# 4040M_V1_0_-_ESP32.net
KiCad netlist of a schematic drawn in EasyEDA Pro
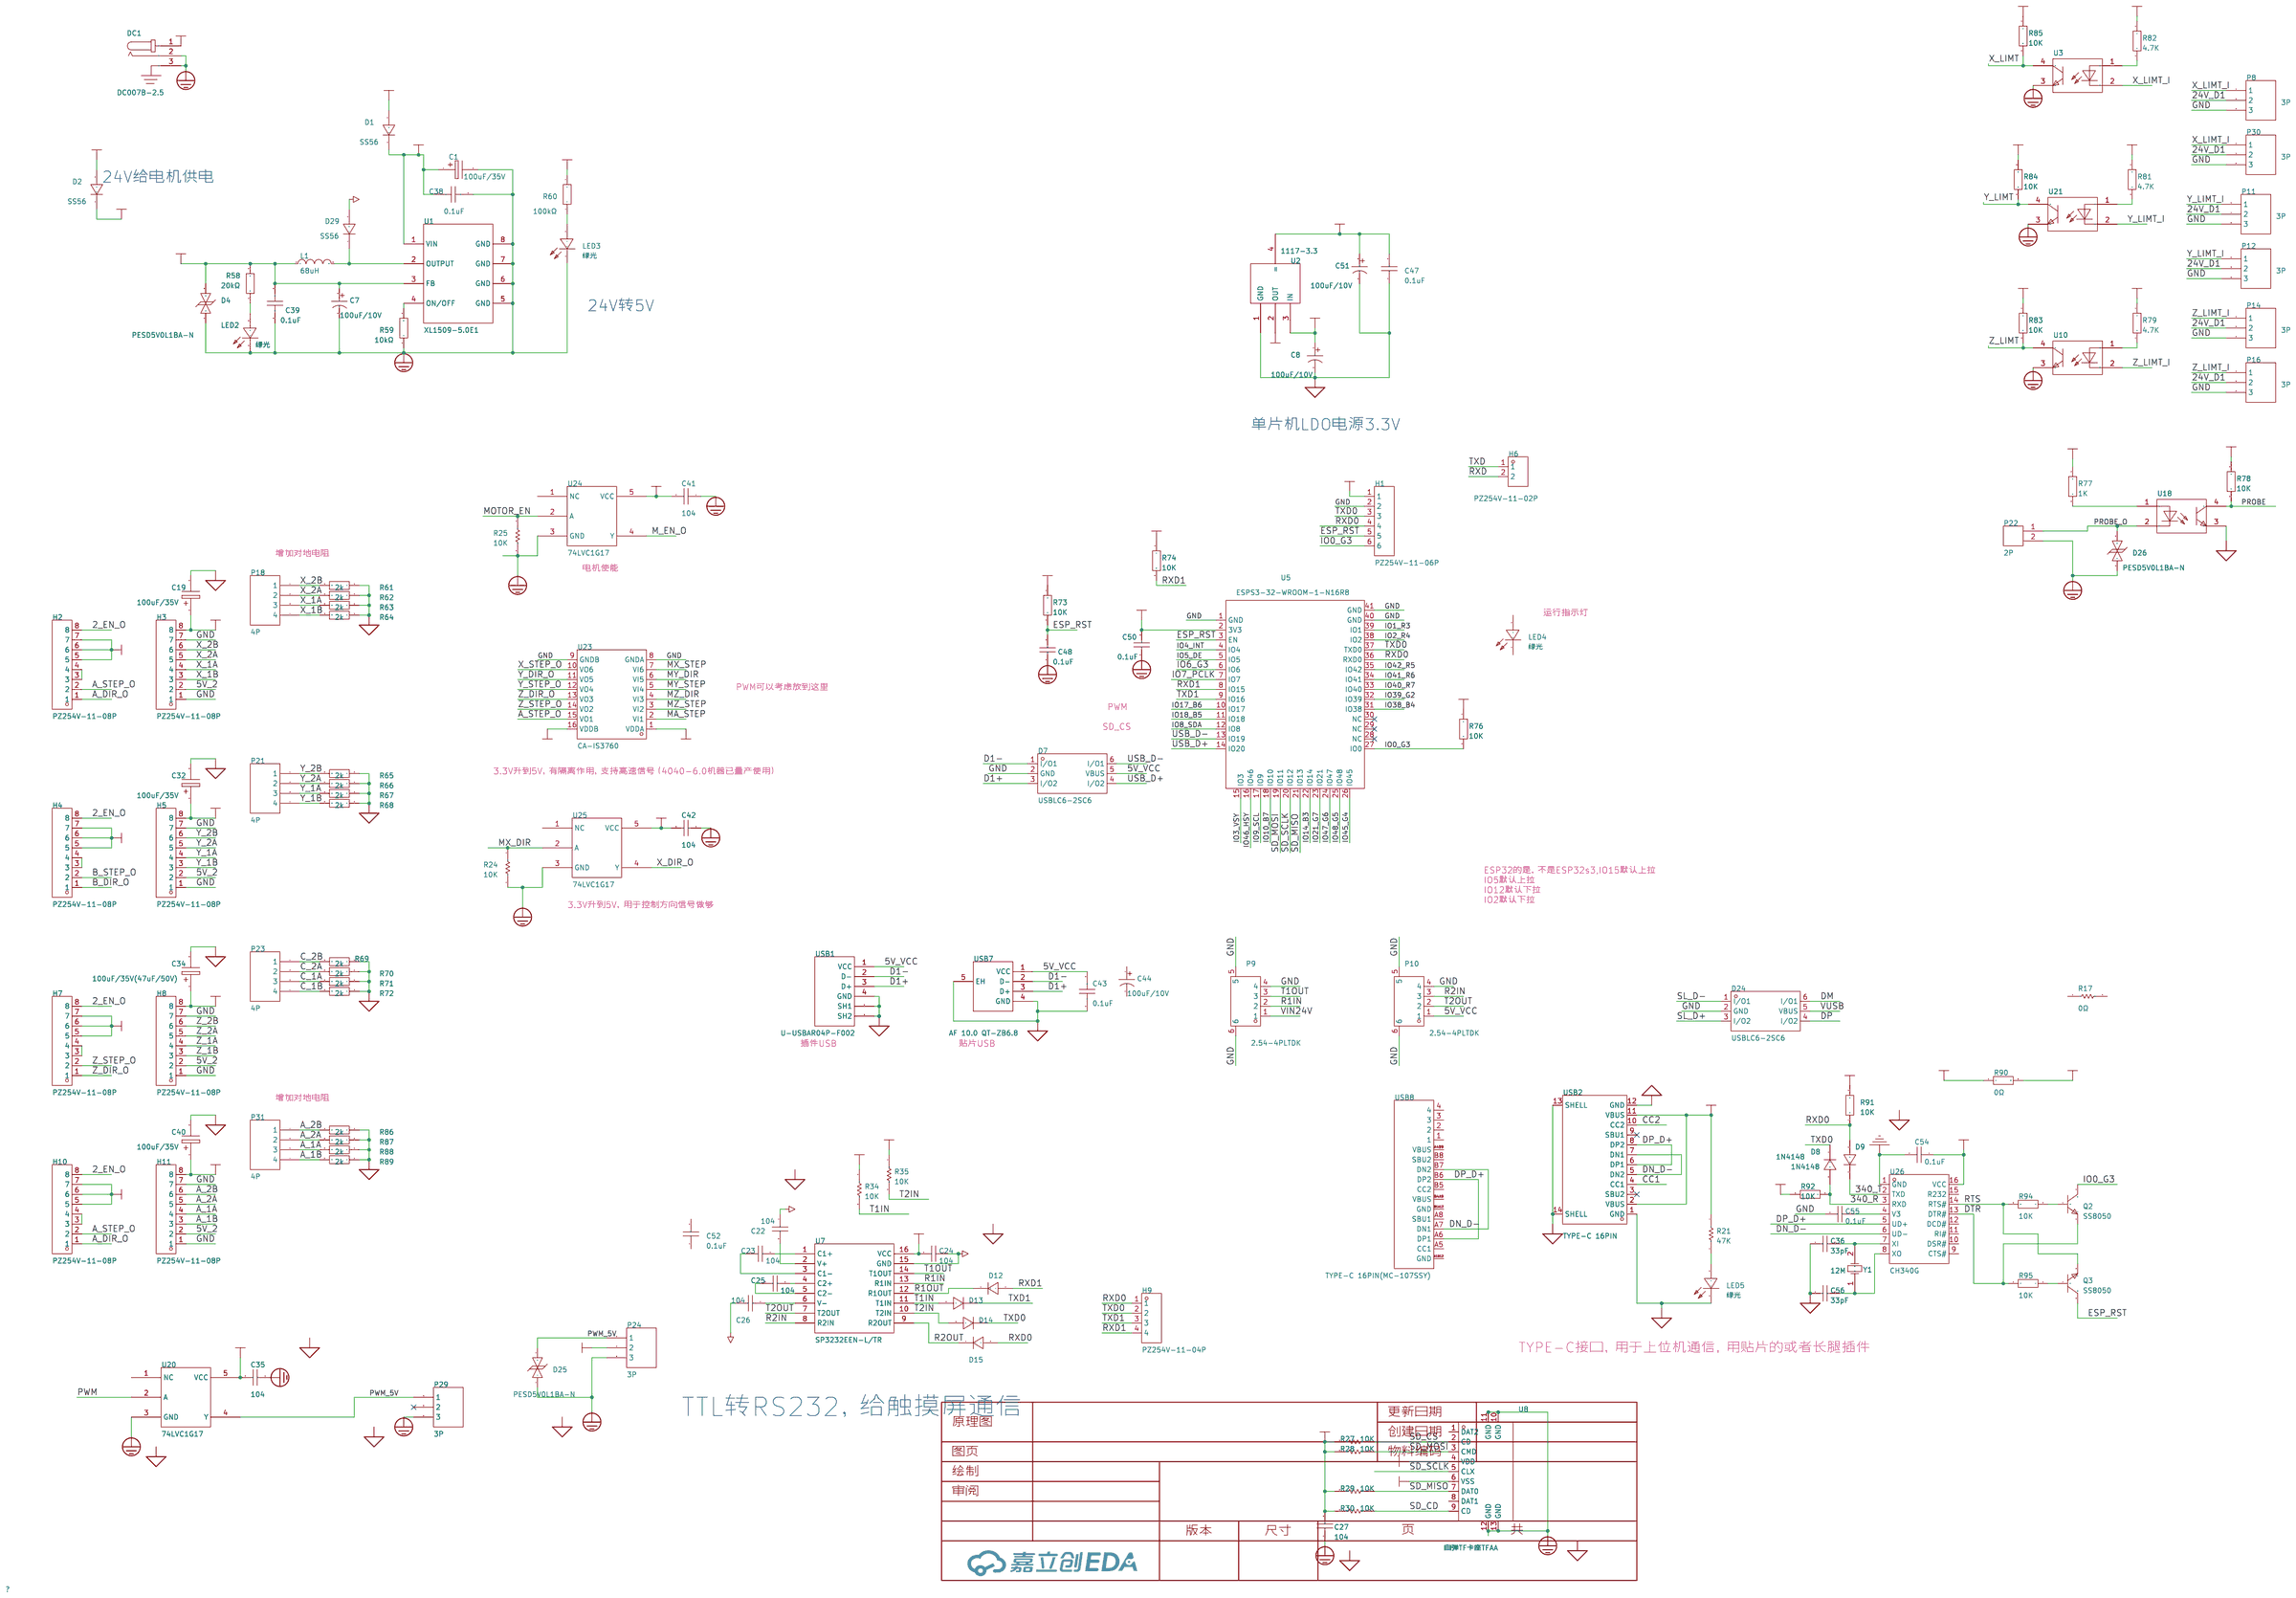
[diagram p0: schematic sheet]

(export (version "E")
  (design (tool "Eeschema 10.0.6"))
  (components
    (comp (ref "C1")
      (value "100uF/35V")
      (footprint "easyedapro:电解电容贴片10x10")
      (libsource (lib "easyedapro") (part "ELECTRO1"))
    )
    (comp (ref "C7")
      (value "100uF/10V")
      (footprint "easyedapro:CAP-SMD_BD5.0-L5.3-W5.3-RD")
      (fields (field (name "Manufacturer Part") "CS1A101M-CRD54") (field (name "Manufacturer") "ST(先科)"))
      (libsource (lib "easyedapro") (part "CS1A101M-CRD54"))
    )
    (comp (ref "C8")
      (value "100uF/10V")
      (footprint "easyedapro:CAP-SMD_BD5.0-L5.3-W5.3-RD")
      (fields (field (name "Manufacturer Part") "CS1A101M-CRD54") (field (name "Manufacturer") "ST(先科)"))
      (libsource (lib "easyedapro") (part "CS1A101M-CRD54"))
    )
    (comp (ref "C19")
      (value "100uF/35V")
      (footprint "easyedapro:电解电容贴片10x10")
      (libsource (lib "easyedapro") (part "ELECTRO1"))
    )
    (comp (ref "C22")
      (value "104")
      (footprint "easyedapro:0603C")
      (description "Capacitor (Semiconductor SIM Model)")
      (libsource (lib "easyedapro") (part "Cap Semi"))
    )
    (comp (ref "C23")
      (value "104")
      (footprint "easyedapro:0603C")
      (description "Capacitor (Semiconductor SIM Model)")
      (libsource (lib "easyedapro") (part "Cap Semi"))
    )
    (comp (ref "C24")
      (value "104")
      (footprint "easyedapro:0603C")
      (description "Capacitor (Semiconductor SIM Model)")
      (libsource (lib "easyedapro") (part "Cap Semi"))
    )
    (comp (ref "C25")
      (value "104")
      (footprint "easyedapro:0603C")
      (description "Capacitor (Semiconductor SIM Model)")
      (libsource (lib "easyedapro") (part "Cap Semi"))
    )
    (comp (ref "C26")
      (value "104")
      (footprint "easyedapro:0603C")
      (description "Capacitor (Semiconductor SIM Model)")
      (libsource (lib "easyedapro") (part "Cap Semi"))
    )
    (comp (ref "C27")
      (value "104")
      (footprint "easyedapro:11")
      (description "Capacitor (Semiconductor SIM Model)")
      (libsource (lib "easyedapro") (part "Cap Semi"))
    )
    (comp (ref "C32")
      (value "100uF/35V")
      (footprint "easyedapro:电解电容贴片10x10")
      (libsource (lib "easyedapro") (part "ELECTRO1"))
    )
    (comp (ref "C34")
      (value "100uF/35V(47uF/50V)")
      (footprint "easyedapro:电解电容贴片10x10")
      (libsource (lib "easyedapro") (part "ELECTRO1"))
    )
    (comp (ref "C35")
      (value "104")
      (footprint "easyedapro:0603C")
      (description "Capacitor (Semiconductor SIM Model)")
      (libsource (lib "easyedapro") (part "Cap Semi"))
    )
    (comp (ref "C36")
      (value "33pF")
      (footprint "easyedapro:C0603")
      (description "容值:12pF;精度:±5%;额定电压:50V;温度系数:C0G;")
      (fields
        (field (name "Manufacturer Part") "CL10C120JB8NNNC")
        (field (name "Manufacturer") "SAMSUNG(三星)")
      )
      (libsource (lib "easyedapro") (part "CL10C120JB8NNNC"))
    )
    (comp (ref "C38")
      (value "0.1uF")
      (footprint "easyedapro:C0603")
      (description "容值:8.2nF;精度:±10%;额定电压:50V;温度系数:X7R;")
      (fields (field (name "Manufacturer Part") "0603B822K500NT") (field (name "Manufacturer") "FH(风华)"))
      (libsource (lib "easyedapro") (part "0603B822K500NT"))
    )
    (comp (ref "C39")
      (value "0.1uF")
      (footprint "easyedapro:C0603")
      (description "容值:8.2nF;精度:±10%;额定电压:50V;温度系数:X7R;")
      (fields (field (name "Manufacturer Part") "0603B822K500NT") (field (name "Manufacturer") "FH(风华)"))
      (libsource (lib "easyedapro") (part "0603B822K500NT"))
    )
    (comp (ref "C40")
      (value "100uF/35V")
      (footprint "easyedapro:电解电容贴片10x10")
      (libsource (lib "easyedapro") (part "ELECTRO1"))
    )
    (comp (ref "C41")
      (value "104")
      (footprint "easyedapro:0603C")
      (description "Capacitor (Semiconductor SIM Model)")
      (libsource (lib "easyedapro") (part "Cap Semi"))
    )
    (comp (ref "C42")
      (value "104")
      (footprint "easyedapro:0603C")
      (description "Capacitor (Semiconductor SIM Model)")
      (libsource (lib "easyedapro") (part "Cap Semi"))
    )
    (comp (ref "C43")
      (value "0.1uF")
      (footprint "easyedapro:C0603")
      (description "容值:8.2nF;精度:±10%;额定电压:50V;温度系数:X7R;")
      (fields (field (name "Manufacturer Part") "0603B822K500NT") (field (name "Manufacturer") "FH(风华)"))
      (libsource (lib "easyedapro") (part "0603B822K500NT"))
    )
    (comp (ref "C44")
      (value "100uF/10V")
      (footprint "easyedapro:CAP-SMD_BD5.0-L5.3-W5.3-RD")
      (fields (field (name "Manufacturer Part") "CS1A101M-CRD54") (field (name "Manufacturer") "ST(先科)"))
      (libsource (lib "easyedapro") (part "CS1A101M-CRD54"))
    )
    (comp (ref "C47")
      (value "0.1uF")
      (footprint "easyedapro:C0603")
      (description "容值:6.8nF;精度:±10%;额定电压:50V;温度系数:X7R;")
      (fields (field (name "Manufacturer Part") "0603B682K500NT") (field (name "Manufacturer") "FH(风华)"))
      (libsource (lib "easyedapro") (part "0603B682K500NT"))
    )
    (comp (ref "C48")
      (value "0.1uF")
      (footprint "easyedapro:C0603")
      (description "容值:6.8nF;精度:±10%;额定电压:50V;温度系数:X7R;")
      (fields (field (name "Manufacturer Part") "0603B682K500NT") (field (name "Manufacturer") "FH(风华)"))
      (libsource (lib "easyedapro") (part "0603B682K500NT"))
    )
    (comp (ref "C50")
      (value "0.1uF")
      (footprint "easyedapro:C0603")
      (description "容值:6.8nF;精度:±10%;额定电压:50V;温度系数:X7R;")
      (fields (field (name "Manufacturer Part") "0603B682K500NT") (field (name "Manufacturer") "FH(风华)"))
      (libsource (lib "easyedapro") (part "0603B682K500NT"))
    )
    (comp (ref "C51")
      (value "100uF/10V")
      (footprint "easyedapro:CAP-SMD_BD5.0-L5.3-W5.3-RD")
      (fields (field (name "Manufacturer Part") "CS1A101M-CRD54") (field (name "Manufacturer") "ST(先科)"))
      (libsource (lib "easyedapro") (part "CS1A101M-CRD54"))
    )
    (comp (ref "C52")
      (value "0.1uF")
      (footprint "easyedapro:C0603")
      (description "容值:6.8nF;精度:±10%;额定电压:50V;温度系数:X7R;")
      (fields (field (name "Manufacturer Part") "0603B682K500NT") (field (name "Manufacturer") "FH(风华)"))
      (libsource (lib "easyedapro") (part "0603B682K500NT"))
    )
    (comp (ref "C54")
      (value "0.1uF")
      (footprint "easyedapro:C0603")
      (description "容值:6.8nF;精度:±10%;额定电压:50V;温度系数:X7R;")
      (fields (field (name "Manufacturer Part") "0603B682K500NT") (field (name "Manufacturer") "FH(风华)"))
      (libsource (lib "easyedapro") (part "0603B682K500NT"))
    )
    (comp (ref "C55")
      (value "0.1uF")
      (footprint "easyedapro:C0603")
      (description "容值:6.8nF;精度:±10%;额定电压:50V;温度系数:X7R;")
      (fields (field (name "Manufacturer Part") "0603B682K500NT") (field (name "Manufacturer") "FH(风华)"))
      (libsource (lib "easyedapro") (part "0603B682K500NT"))
    )
    (comp (ref "C56")
      (value "33pF")
      (footprint "easyedapro:C0603")
      (description "容值:12pF;精度:±5%;额定电压:50V;温度系数:C0G;")
      (fields
        (field (name "Manufacturer Part") "CL10C120JB8NNNC")
        (field (name "Manufacturer") "SAMSUNG(三星)")
      )
      (libsource (lib "easyedapro") (part "CL10C120JB8NNNC"))
    )
    (comp (ref "D1")
      (value "SS56")
      (footprint "easyedapro:SMA_L4.3-W2.6-LS5.2-RD")
      (libsource (lib "easyedapro") (part "SS34-SMA"))
    )
    (comp (ref "D2")
      (value "SS56")
      (footprint "easyedapro:SMA_L4.3-W2.6-LS5.2-RD")
      (libsource (lib "easyedapro") (part "SS34-SMA"))
    )
    (comp (ref "D4")
      (value "PESD5V0L1BA-N")
      (footprint "easyedapro:SOD-523_L1.2-W0.8-LS1.6-BI")
      (description "极性:Bidirectional;反向关断电压（典型值）:5V (Max);击穿电压（最小值）:6V;箝位电压:15V;峰值脉冲电流（10/1000us）:5A (8/20us);")
      (fields (field (name "Manufacturer") "BORN伯恩半导体"))
      (libsource (lib "easyedapro") (part "PESD5V0S1BBN"))
    )
    (comp (ref "D7")
      (value "USBLC6-2SC6")
      (footprint "easyedapro:SOT-23-6_L2.9-W1.6-P0.95-LS2.8-BL")
      (description "最大钳位电压:15V;击穿电压:6V;")
      (fields (field (name "Manufacturer") "UMW(友台半导体)"))
      (libsource (lib "easyedapro") (part "USBLC6-2SC6_C2687116"))
    )
    (comp (ref "D8")
      (value "1N4148")
      (footprint "easyedapro:SOD-323_L1.8-W1.3-LS2.5-RD")
      (description "二极管配置:独立式;正向压降(Vf):1.25V@150mA;直流反向耐压(Vr):100V;整流电流:150mA;反向恢复时间(Trr):4ns;")
      (fields (field (name "Manufacturer") "CJ(江苏长电/长晶)"))
      (libsource (lib "easyedapro") (part "1N4148WS T4"))
    )
    (comp (ref "D9")
      (value "1N4148")
      (footprint "easyedapro:SOD-323_L1.8-W1.3-LS2.5-RD")
      (description "二极管配置:独立式;正向压降(Vf):1.25V@150mA;直流反向耐压(Vr):100V;整流电流:150mA;反向恢复时间(Trr):4ns;")
      (fields (field (name "Manufacturer") "CJ(江苏长电/长晶)"))
      (libsource (lib "easyedapro") (part "1N4148WS T4"))
    )
    (comp (ref "D12")
      (value "1N4148WS")
      (footprint "easyedapro:SOD-323_L1.8-W1.3-LS2.5-RD")
      (description "二极管配置:独立式;正向压降(Vf):1.25V@150mA;直流反向耐压(Vr):100V;整流电流:150mA;反向恢复时间(Trr):4ns;")
      (fields (field (name "Manufacturer") "CJ(江苏长电/长晶)"))
      (libsource (lib "easyedapro") (part "1N4148WS T4"))
    )
    (comp (ref "D13")
      (value "1N4148WS")
      (footprint "easyedapro:SOD-323_L1.8-W1.3-LS2.5-RD")
      (description "二极管配置:独立式;正向压降(Vf):1.25V@150mA;直流反向耐压(Vr):100V;整流电流:150mA;反向恢复时间(Trr):4ns;")
      (fields (field (name "Manufacturer") "CJ(江苏长电/长晶)"))
      (libsource (lib "easyedapro") (part "1N4148WS T4"))
    )
    (comp (ref "D14")
      (value "1N4148WS")
      (footprint "easyedapro:SOD-323_L1.8-W1.3-LS2.5-RD")
      (description "二极管配置:独立式;正向压降(Vf):1.25V@150mA;直流反向耐压(Vr):100V;整流电流:150mA;反向恢复时间(Trr):4ns;")
      (fields (field (name "Manufacturer") "CJ(江苏长电/长晶)"))
      (libsource (lib "easyedapro") (part "1N4148WS T4"))
    )
    (comp (ref "D15")
      (value "1N4148WS")
      (footprint "easyedapro:SOD-323_L1.8-W1.3-LS2.5-RD")
      (description "二极管配置:独立式;正向压降(Vf):1.25V@150mA;直流反向耐压(Vr):100V;整流电流:150mA;反向恢复时间(Trr):4ns;")
      (fields (field (name "Manufacturer") "CJ(江苏长电/长晶)"))
      (libsource (lib "easyedapro") (part "1N4148WS T4"))
    )
    (comp (ref "D24")
      (value "USBLC6-2SC6")
      (footprint "easyedapro:SOT-23-6_L2.9-W1.6-P0.95-LS2.8-BL")
      (description "最大钳位电压:15V;击穿电压:6V;")
      (fields (field (name "Manufacturer") "UMW(友台半导体)"))
      (libsource (lib "easyedapro") (part "USBLC6-2SC6_C2687116"))
    )
    (comp (ref "D25")
      (value "PESD5V0L1BA-N")
      (footprint "easyedapro:SOD-523_L1.2-W0.8-LS1.6-BI")
      (description "极性:Bidirectional;反向关断电压（典型值）:5V (Max);击穿电压（最小值）:6V;箝位电压:15V;峰值脉冲电流（10/1000us）:5A (8/20us);")
      (fields (field (name "Manufacturer") "BORN伯恩半导体"))
      (libsource (lib "easyedapro") (part "PESD5V0S1BBN"))
    )
    (comp (ref "D26")
      (value "PESD5V0L1BA-N")
      (footprint "easyedapro:SOD-523_L1.2-W0.8-LS1.6-BI")
      (description "极性:Bidirectional;反向关断电压（典型值）:5V (Max);击穿电压（最小值）:6V;箝位电压:15V;峰值脉冲电流（10/1000us）:5A (8/20us);")
      (fields (field (name "Manufacturer") "BORN伯恩半导体"))
      (libsource (lib "easyedapro") (part "PESD5V0S1BBN"))
    )
    (comp (ref "D29")
      (value "SS56")
      (footprint "easyedapro:SMA_L4.3-W2.6-LS5.2-RD")
      (libsource (lib "easyedapro") (part "SS34-SMA"))
    )
    (comp (ref "DC1")
      (value "DC007B-2.5")
      (footprint "easyedapro:DC-IN-TH_HX-DC007B-2.5")
      (description "连接器类型:DC电源插座;安装方式:弯插;触点内径:2.5mm;触点外径:7.7mm;额定电流:5A;额定电压:20V;工作温度:-25°C~+70°C;")
      (fields (field (name "Manufacturer") "SHOU HAN(首韩)"))
      (libsource (lib "easyedapro") (part "DC007B-2.5"))
    )
    (comp (ref "H1")
      (value "PZ254V-11-06P")
      (footprint "easyedapro:HDR-TH_6P-P2.54-V-M")
      (fields (field (name "Manufacturer") "XFCN(兴飞)"))
      (libsource (lib "easyedapro") (part "PZ254V-11-06P"))
    )
    (comp (ref "H2")
      (value "PZ254V-11-08P")
      (footprint "easyedapro:HDR-TH_8P-P2.54-V-M")
      (fields (field (name "Manufacturer") "XFCN(兴飞)"))
      (libsource (lib "easyedapro") (part "PZ254V-11-08P"))
    )
    (comp (ref "H3")
      (value "PZ254V-11-08P")
      (footprint "easyedapro:HDR-TH_8P-P2.54-V-M")
      (fields (field (name "Manufacturer") "XFCN(兴飞)"))
      (libsource (lib "easyedapro") (part "PZ254V-11-08P"))
    )
    (comp (ref "H4")
      (value "PZ254V-11-08P")
      (footprint "easyedapro:HDR-TH_8P-P2.54-V-M")
      (fields (field (name "Manufacturer") "XFCN(兴飞)"))
      (libsource (lib "easyedapro") (part "PZ254V-11-08P"))
    )
    (comp (ref "H5")
      (value "PZ254V-11-08P")
      (footprint "easyedapro:HDR-TH_8P-P2.54-V-M")
      (fields (field (name "Manufacturer") "XFCN(兴飞)"))
      (libsource (lib "easyedapro") (part "PZ254V-11-08P"))
    )
    (comp (ref "H6")
      (value "PZ254V-11-02P")
      (footprint "easyedapro:HDR-TH_2P-P2.54-V-M")
      (fields (field (name "Manufacturer") "XFCN(兴飞)"))
      (libsource (lib "easyedapro") (part "PZ254V-11-02P"))
    )
    (comp (ref "H7")
      (value "PZ254V-11-08P")
      (footprint "easyedapro:HDR-TH_8P-P2.54-V-M")
      (fields (field (name "Manufacturer") "XFCN(兴飞)"))
      (libsource (lib "easyedapro") (part "PZ254V-11-08P"))
    )
    (comp (ref "H8")
      (value "PZ254V-11-08P")
      (footprint "easyedapro:HDR-TH_8P-P2.54-V-M")
      (fields (field (name "Manufacturer") "XFCN(兴飞)"))
      (libsource (lib "easyedapro") (part "PZ254V-11-08P"))
    )
    (comp (ref "H9")
      (value "PZ254V-11-04P")
      (footprint "easyedapro:HDR-TH_4P-P2.54-V-M")
      (fields (field (name "Manufacturer") "XFCN(兴飞)"))
      (libsource (lib "easyedapro") (part "PZ254V-11-04P_C2691448"))
    )
    (comp (ref "H10")
      (value "PZ254V-11-08P")
      (footprint "easyedapro:HDR-TH_8P-P2.54-V-M")
      (fields (field (name "Manufacturer") "XFCN(兴飞)"))
      (libsource (lib "easyedapro") (part "PZ254V-11-08P"))
    )
    (comp (ref "H11")
      (value "PZ254V-11-08P")
      (footprint "easyedapro:HDR-TH_8P-P2.54-V-M")
      (fields (field (name "Manufacturer") "XFCN(兴飞)"))
      (libsource (lib "easyedapro") (part "PZ254V-11-08P"))
    )
    (comp (ref "L1")
      (value "68uH")
      (footprint "easyedapro:IND-SMD_L7.0-W7.0_SMDRI74-330MT")
      (description "电感值:33uH;精度:±20%;额定电流:960mA;饱和电流(Isat):1.8A;类型:屏蔽电感;")
      (fields (field (name "Manufacturer Part") "SMDRI74-330MT") (field (name "Manufacturer") "SXN(顺翔诺)"))
      (libsource (lib "easyedapro") (part "SMDRI74-330MT"))
    )
    (comp (ref "LED2")
      (value "绿光")
      (footprint "easyedapro:LED0603-RD")
      (fields (field (name "Manufacturer") "KENTO"))
      (libsource (lib "easyedapro") (part "KT-0603R"))
    )
    (comp (ref "LED3")
      (value "绿光")
      (footprint "easyedapro:LED0603-RD")
      (fields (field (name "Manufacturer") "KENTO"))
      (libsource (lib "easyedapro") (part "KT-0603R"))
    )
    (comp (ref "LED4")
      (value "绿光")
      (footprint "easyedapro:LED0603-RD")
      (fields (field (name "Manufacturer") "KENTO"))
      (libsource (lib "easyedapro") (part "KT-0603R"))
    )
    (comp (ref "LED5")
      (value "绿光")
      (footprint "easyedapro:LED0603-RD")
      (fields (field (name "Manufacturer") "KENTO"))
      (libsource (lib "easyedapro") (part "KT-0603R"))
    )
    (comp (ref "P8")
      (value "3P")
      (footprint "easyedapro:HDR1X3_CON")
      (libsource (lib "easyedapro") (part "3P"))
    )
    (comp (ref "P9")
      (value "2.54-4PLTDK")
      (footprint "easyedapro:CONN-SMD_4P-P2.50_SHOU_2.54-4PLTDK")
      (fields (field (name "Manufacturer") "SHOU HAN(首韩)"))
      (libsource (lib "easyedapro") (part "2.54-4PLTDK"))
    )
    (comp (ref "P10")
      (value "2.54-4PLTDK")
      (footprint "easyedapro:CONN-SMD_4P-P2.50_SHOU_2.54-4PLTDK")
      (fields (field (name "Manufacturer") "SHOU HAN(首韩)"))
      (libsource (lib "easyedapro") (part "2.54-4PLTDK"))
    )
    (comp (ref "P11")
      (value "3P")
      (footprint "easyedapro:HDR1X3_CON")
      (libsource (lib "easyedapro") (part "3P"))
    )
    (comp (ref "P12")
      (value "3P")
      (footprint "easyedapro:HDR1X3_CON")
      (libsource (lib "easyedapro") (part "3P"))
    )
    (comp (ref "P14")
      (value "3P")
      (footprint "easyedapro:HDR1X3_CON")
      (libsource (lib "easyedapro") (part "3P"))
    )
    (comp (ref "P16")
      (value "3P")
      (footprint "easyedapro:HDR1X3_CON")
      (libsource (lib "easyedapro") (part "3P"))
    )
    (comp (ref "P18")
      (value "4P")
      (footprint "easyedapro:HDR1X4_CON")
      (libsource (lib "easyedapro") (part "4P"))
    )
    (comp (ref "P21")
      (value "4P")
      (footprint "easyedapro:HDR1X4_CON")
      (libsource (lib "easyedapro") (part "4P"))
    )
    (comp (ref "P22") (value "2P") (libsource (lib "easyedapro") (part "2P")))
    (comp (ref "P23")
      (value "4P")
      (footprint "easyedapro:HDR1X4_CON")
      (libsource (lib "easyedapro") (part "4P"))
    )
    (comp (ref "P24")
      (value "3P")
      (footprint "easyedapro:HDR1X3_CON")
      (libsource (lib "easyedapro") (part "3P"))
    )
    (comp (ref "P29")
      (value "3P")
      (footprint "easyedapro:HDR1X3_CON")
      (libsource (lib "easyedapro") (part "3P"))
    )
    (comp (ref "P30")
      (value "3P")
      (footprint "easyedapro:HDR1X3_CON")
      (libsource (lib "easyedapro") (part "3P"))
    )
    (comp (ref "P31")
      (value "4P")
      (footprint "easyedapro:HDR1X4_CON")
      (libsource (lib "easyedapro") (part "4P"))
    )
    (comp (ref "Q2")
      (value "SS8050")
      (footprint "easyedapro:SOT-23-3_L2.9-W1.3-P1.90-LS2.4-BR")
      (fields (field (name "Manufacturer") "Doeshare(德芯)"))
      (libsource (lib "easyedapro") (part "SS8050_C2931717"))
    )
    (comp (ref "Q3")
      (value "SS8050")
      (footprint "easyedapro:SOT-23-3_L2.9-W1.3-P1.90-LS2.4-BR")
      (fields (field (name "Manufacturer") "Doeshare(德芯)"))
      (libsource (lib "easyedapro") (part "SS8050_C2931717"))
    )
    (comp (ref "R17")
      (value "0Ω")
      (footprint "easyedapro:10")
      (description "Resistor")
      (libsource (lib "easyedapro") (part "RES"))
    )
    (comp (ref "R21")
      (value "47K")
      (footprint "easyedapro:10")
      (description "Resistor")
      (libsource (lib "easyedapro") (part "RES"))
    )
    (comp (ref "R24")
      (value "10K")
      (description "Resistor")
      (fields (field (name "Publisher") "Altium Limited"))
      (libsource (lib "") (part "RES_1"))
    )
    (comp (ref "R25")
      (value "10K")
      (description "Resistor")
      (fields (field (name "Publisher") "Altium Limited"))
      (libsource (lib "") (part "RES_1"))
    )
    (comp (ref "R27")
      (value "10K")
      (footprint "easyedapro:10")
      (description "Resistor")
      (libsource (lib "easyedapro") (part "RES"))
    )
    (comp (ref "R28")
      (value "10K")
      (footprint "easyedapro:10")
      (description "Resistor")
      (libsource (lib "easyedapro") (part "RES"))
    )
    (comp (ref "R29")
      (value "10K")
      (footprint "easyedapro:10")
      (description "Resistor")
      (libsource (lib "easyedapro") (part "RES"))
    )
    (comp (ref "R30")
      (value "10K")
      (footprint "easyedapro:10")
      (description "Resistor")
      (libsource (lib "easyedapro") (part "RES"))
    )
    (comp (ref "R34")
      (value "10K")
      (footprint "easyedapro:10")
      (description "Resistor")
      (libsource (lib "easyedapro") (part "RES"))
    )
    (comp (ref "R35")
      (value "10K")
      (footprint "easyedapro:10")
      (description "Resistor")
      (libsource (lib "easyedapro") (part "RES"))
    )
    (comp (ref "R58")
      (value "20kΩ")
      (footprint "easyedapro:R0603")
      (description "电阻类型:厚膜电阻;阻值:24kΩ;精度:±1%;功率:100mW;工作电压:75V;温度系数:±100ppm/°C;")
      (fields
        (field (name "Manufacturer Part") "0603WAF2402T5E")
        (field (name "Manufacturer") "UNI-ROYAL(厚声)")
      )
      (libsource (lib "easyedapro") (part "0603WAF2402T5E"))
    )
    (comp (ref "R59")
      (value "10kΩ")
      (footprint "easyedapro:R0603")
      (description "电阻类型:厚膜电阻;阻值:24kΩ;精度:±1%;功率:100mW;工作电压:75V;温度系数:±100ppm/°C;")
      (fields
        (field (name "Manufacturer Part") "0603WAF2402T5E")
        (field (name "Manufacturer") "UNI-ROYAL(厚声)")
      )
      (libsource (lib "easyedapro") (part "0603WAF2402T5E"))
    )
    (comp (ref "R60")
      (value "100kΩ")
      (footprint "easyedapro:R0603")
      (description "电阻类型:厚膜电阻;阻值:24kΩ;精度:±1%;功率:100mW;工作电压:75V;温度系数:±100ppm/°C;")
      (fields
        (field (name "Manufacturer Part") "0603WAF2402T5E")
        (field (name "Manufacturer") "UNI-ROYAL(厚声)")
      )
      (libsource (lib "easyedapro") (part "0603WAF2402T5E"))
    )
    (comp (ref "R61")
      (value "2k")
      (footprint "easyedapro:R0603")
      (description "电阻类型:厚膜电阻;阻值:24kΩ;精度:±1%;功率:100mW;工作电压:75V;温度系数:±100ppm/°C;")
      (fields
        (field (name "Manufacturer Part") "0603WAF2402T5E")
        (field (name "Manufacturer") "UNI-ROYAL(厚声)")
      )
      (libsource (lib "easyedapro") (part "0603WAF2402T5E"))
    )
    (comp (ref "R62")
      (value "2k")
      (footprint "easyedapro:R0603")
      (description "电阻类型:厚膜电阻;阻值:24kΩ;精度:±1%;功率:100mW;工作电压:75V;温度系数:±100ppm/°C;")
      (fields
        (field (name "Manufacturer Part") "0603WAF2402T5E")
        (field (name "Manufacturer") "UNI-ROYAL(厚声)")
      )
      (libsource (lib "easyedapro") (part "0603WAF2402T5E"))
    )
    (comp (ref "R63")
      (value "2k")
      (footprint "easyedapro:R0603")
      (description "电阻类型:厚膜电阻;阻值:24kΩ;精度:±1%;功率:100mW;工作电压:75V;温度系数:±100ppm/°C;")
      (fields
        (field (name "Manufacturer Part") "0603WAF2402T5E")
        (field (name "Manufacturer") "UNI-ROYAL(厚声)")
      )
      (libsource (lib "easyedapro") (part "0603WAF2402T5E"))
    )
    (comp (ref "R64")
      (value "2k")
      (footprint "easyedapro:R0603")
      (description "电阻类型:厚膜电阻;阻值:24kΩ;精度:±1%;功率:100mW;工作电压:75V;温度系数:±100ppm/°C;")
      (fields
        (field (name "Manufacturer Part") "0603WAF2402T5E")
        (field (name "Manufacturer") "UNI-ROYAL(厚声)")
      )
      (libsource (lib "easyedapro") (part "0603WAF2402T5E"))
    )
    (comp (ref "R65")
      (value "2k")
      (footprint "easyedapro:R0603")
      (description "电阻类型:厚膜电阻;阻值:24kΩ;精度:±1%;功率:100mW;工作电压:75V;温度系数:±100ppm/°C;")
      (fields
        (field (name "Manufacturer Part") "0603WAF2402T5E")
        (field (name "Manufacturer") "UNI-ROYAL(厚声)")
      )
      (libsource (lib "easyedapro") (part "0603WAF2402T5E"))
    )
    (comp (ref "R66")
      (value "2k")
      (footprint "easyedapro:R0603")
      (description "电阻类型:厚膜电阻;阻值:24kΩ;精度:±1%;功率:100mW;工作电压:75V;温度系数:±100ppm/°C;")
      (fields
        (field (name "Manufacturer Part") "0603WAF2402T5E")
        (field (name "Manufacturer") "UNI-ROYAL(厚声)")
      )
      (libsource (lib "easyedapro") (part "0603WAF2402T5E"))
    )
    (comp (ref "R67")
      (value "2k")
      (footprint "easyedapro:R0603")
      (description "电阻类型:厚膜电阻;阻值:24kΩ;精度:±1%;功率:100mW;工作电压:75V;温度系数:±100ppm/°C;")
      (fields
        (field (name "Manufacturer Part") "0603WAF2402T5E")
        (field (name "Manufacturer") "UNI-ROYAL(厚声)")
      )
      (libsource (lib "easyedapro") (part "0603WAF2402T5E"))
    )
    (comp (ref "R68")
      (value "2k")
      (footprint "easyedapro:R0603")
      (description "电阻类型:厚膜电阻;阻值:24kΩ;精度:±1%;功率:100mW;工作电压:75V;温度系数:±100ppm/°C;")
      (fields
        (field (name "Manufacturer Part") "0603WAF2402T5E")
        (field (name "Manufacturer") "UNI-ROYAL(厚声)")
      )
      (libsource (lib "easyedapro") (part "0603WAF2402T5E"))
    )
    (comp (ref "R69")
      (value "2k")
      (footprint "easyedapro:R0603")
      (description "电阻类型:厚膜电阻;阻值:24kΩ;精度:±1%;功率:100mW;工作电压:75V;温度系数:±100ppm/°C;")
      (fields
        (field (name "Manufacturer Part") "0603WAF2402T5E")
        (field (name "Manufacturer") "UNI-ROYAL(厚声)")
      )
      (libsource (lib "easyedapro") (part "0603WAF2402T5E"))
    )
    (comp (ref "R70")
      (value "2k")
      (footprint "easyedapro:R0603")
      (description "电阻类型:厚膜电阻;阻值:24kΩ;精度:±1%;功率:100mW;工作电压:75V;温度系数:±100ppm/°C;")
      (fields
        (field (name "Manufacturer Part") "0603WAF2402T5E")
        (field (name "Manufacturer") "UNI-ROYAL(厚声)")
      )
      (libsource (lib "easyedapro") (part "0603WAF2402T5E"))
    )
    (comp (ref "R71")
      (value "2k")
      (footprint "easyedapro:R0603")
      (description "电阻类型:厚膜电阻;阻值:24kΩ;精度:±1%;功率:100mW;工作电压:75V;温度系数:±100ppm/°C;")
      (fields
        (field (name "Manufacturer Part") "0603WAF2402T5E")
        (field (name "Manufacturer") "UNI-ROYAL(厚声)")
      )
      (libsource (lib "easyedapro") (part "0603WAF2402T5E"))
    )
    (comp (ref "R72")
      (value "2k")
      (footprint "easyedapro:R0603")
      (description "电阻类型:厚膜电阻;阻值:24kΩ;精度:±1%;功率:100mW;工作电压:75V;温度系数:±100ppm/°C;")
      (fields
        (field (name "Manufacturer Part") "0603WAF2402T5E")
        (field (name "Manufacturer") "UNI-ROYAL(厚声)")
      )
      (libsource (lib "easyedapro") (part "0603WAF2402T5E"))
    )
    (comp (ref "R73")
      (value "10K")
      (footprint "easyedapro:R0603")
      (description "电阻类型:厚膜电阻;阻值:24kΩ;精度:±1%;功率:100mW;工作电压:75V;温度系数:±100ppm/°C;")
      (fields
        (field (name "Manufacturer Part") "0603WAF2402T5E")
        (field (name "Manufacturer") "UNI-ROYAL(厚声)")
      )
      (libsource (lib "easyedapro") (part "0603WAF2402T5E"))
    )
    (comp (ref "R74")
      (value "10K")
      (footprint "easyedapro:R0603")
      (description "电阻类型:厚膜电阻;阻值:24kΩ;精度:±1%;功率:100mW;工作电压:75V;温度系数:±100ppm/°C;")
      (fields
        (field (name "Manufacturer Part") "0603WAF2402T5E")
        (field (name "Manufacturer") "UNI-ROYAL(厚声)")
      )
      (libsource (lib "easyedapro") (part "0603WAF2402T5E"))
    )
    (comp (ref "R76")
      (value "10K")
      (footprint "easyedapro:R0603")
      (description "电阻类型:厚膜电阻;阻值:24kΩ;精度:±1%;功率:100mW;工作电压:75V;温度系数:±100ppm/°C;")
      (fields
        (field (name "Manufacturer Part") "0603WAF2402T5E")
        (field (name "Manufacturer") "UNI-ROYAL(厚声)")
      )
      (libsource (lib "easyedapro") (part "0603WAF2402T5E"))
    )
    (comp (ref "R77")
      (value "1K")
      (footprint "easyedapro:R0603")
      (description "电阻类型:厚膜电阻;阻值:24kΩ;精度:±1%;功率:100mW;工作电压:75V;温度系数:±100ppm/°C;")
      (fields
        (field (name "Manufacturer Part") "0603WAF2402T5E")
        (field (name "Manufacturer") "UNI-ROYAL(厚声)")
      )
      (libsource (lib "easyedapro") (part "0603WAF2402T5E"))
    )
    (comp (ref "R78")
      (value "10K")
      (footprint "easyedapro:R0603")
      (description "电阻类型:厚膜电阻;阻值:24kΩ;精度:±1%;功率:100mW;工作电压:75V;温度系数:±100ppm/°C;")
      (fields
        (field (name "Manufacturer Part") "0603WAF2402T5E")
        (field (name "Manufacturer") "UNI-ROYAL(厚声)")
      )
      (libsource (lib "easyedapro") (part "0603WAF2402T5E"))
    )
    (comp (ref "R79")
      (value "4.7K")
      (footprint "easyedapro:R0603")
      (description "电阻类型:厚膜电阻;阻值:24kΩ;精度:±1%;功率:100mW;工作电压:75V;温度系数:±100ppm/°C;")
      (fields
        (field (name "Manufacturer Part") "0603WAF2402T5E")
        (field (name "Manufacturer") "UNI-ROYAL(厚声)")
      )
      (libsource (lib "easyedapro") (part "0603WAF2402T5E"))
    )
    (comp (ref "R81")
      (value "4.7K")
      (footprint "easyedapro:R0603")
      (description "电阻类型:厚膜电阻;阻值:24kΩ;精度:±1%;功率:100mW;工作电压:75V;温度系数:±100ppm/°C;")
      (fields
        (field (name "Manufacturer Part") "0603WAF2402T5E")
        (field (name "Manufacturer") "UNI-ROYAL(厚声)")
      )
      (libsource (lib "easyedapro") (part "0603WAF2402T5E"))
    )
    (comp (ref "R82")
      (value "4.7K")
      (footprint "easyedapro:R0603")
      (description "电阻类型:厚膜电阻;阻值:24kΩ;精度:±1%;功率:100mW;工作电压:75V;温度系数:±100ppm/°C;")
      (fields
        (field (name "Manufacturer Part") "0603WAF2402T5E")
        (field (name "Manufacturer") "UNI-ROYAL(厚声)")
      )
      (libsource (lib "easyedapro") (part "0603WAF2402T5E"))
    )
    (comp (ref "R83")
      (value "47K")
      (footprint "easyedapro:R0603")
      (description "电阻类型:厚膜电阻;阻值:24kΩ;精度:±1%;功率:100mW;工作电压:75V;温度系数:±100ppm/°C;")
      (fields
        (field (name "Manufacturer Part") "0603WAF2402T5E")
        (field (name "Manufacturer") "UNI-ROYAL(厚声)")
      )
      (libsource (lib "easyedapro") (part "0603WAF2402T5E"))
    )
    (comp (ref "R84")
      (value "47K")
      (footprint "easyedapro:R0603")
      (description "电阻类型:厚膜电阻;阻值:24kΩ;精度:±1%;功率:100mW;工作电压:75V;温度系数:±100ppm/°C;")
      (fields
        (field (name "Manufacturer Part") "0603WAF2402T5E")
        (field (name "Manufacturer") "UNI-ROYAL(厚声)")
      )
      (libsource (lib "easyedapro") (part "0603WAF2402T5E"))
    )
    (comp (ref "R85")
      (value "47K")
      (footprint "easyedapro:R0603")
      (description "电阻类型:厚膜电阻;阻值:24kΩ;精度:±1%;功率:100mW;工作电压:75V;温度系数:±100ppm/°C;")
      (fields
        (field (name "Manufacturer Part") "0603WAF2402T5E")
        (field (name "Manufacturer") "UNI-ROYAL(厚声)")
      )
      (libsource (lib "easyedapro") (part "0603WAF2402T5E"))
    )
    (comp (ref "R86")
      (value "2k")
      (footprint "easyedapro:R0603")
      (description "电阻类型:厚膜电阻;阻值:24kΩ;精度:±1%;功率:100mW;工作电压:75V;温度系数:±100ppm/°C;")
      (fields
        (field (name "Manufacturer Part") "0603WAF2402T5E")
        (field (name "Manufacturer") "UNI-ROYAL(厚声)")
      )
      (libsource (lib "easyedapro") (part "0603WAF2402T5E"))
    )
    (comp (ref "R87")
      (value "2k")
      (footprint "easyedapro:R0603")
      (description "电阻类型:厚膜电阻;阻值:24kΩ;精度:±1%;功率:100mW;工作电压:75V;温度系数:±100ppm/°C;")
      (fields
        (field (name "Manufacturer Part") "0603WAF2402T5E")
        (field (name "Manufacturer") "UNI-ROYAL(厚声)")
      )
      (libsource (lib "easyedapro") (part "0603WAF2402T5E"))
    )
    (comp (ref "R88")
      (value "2k")
      (footprint "easyedapro:R0603")
      (description "电阻类型:厚膜电阻;阻值:24kΩ;精度:±1%;功率:100mW;工作电压:75V;温度系数:±100ppm/°C;")
      (fields
        (field (name "Manufacturer Part") "0603WAF2402T5E")
        (field (name "Manufacturer") "UNI-ROYAL(厚声)")
      )
      (libsource (lib "easyedapro") (part "0603WAF2402T5E"))
    )
    (comp (ref "R89")
      (value "2k")
      (footprint "easyedapro:R0603")
      (description "电阻类型:厚膜电阻;阻值:24kΩ;精度:±1%;功率:100mW;工作电压:75V;温度系数:±100ppm/°C;")
      (fields
        (field (name "Manufacturer Part") "0603WAF2402T5E")
        (field (name "Manufacturer") "UNI-ROYAL(厚声)")
      )
      (libsource (lib "easyedapro") (part "0603WAF2402T5E"))
    )
    (comp (ref "R90")
      (value "0Ω")
      (footprint "easyedapro:R0603")
      (description "电阻类型:厚膜电阻;阻值:24kΩ;精度:±1%;功率:100mW;工作电压:75V;温度系数:±100ppm/°C;")
      (fields
        (field (name "Manufacturer Part") "0603WAF2402T5E")
        (field (name "Manufacturer") "UNI-ROYAL(厚声)")
      )
      (libsource (lib "easyedapro") (part "0603WAF2402T5E"))
    )
    (comp (ref "R91")
      (value "10K")
      (footprint "easyedapro:R0603")
      (description "电阻类型:厚膜电阻;阻值:24kΩ;精度:±1%;功率:100mW;工作电压:75V;温度系数:±100ppm/°C;")
      (fields
        (field (name "Manufacturer Part") "0603WAF2402T5E")
        (field (name "Manufacturer") "UNI-ROYAL(厚声)")
      )
      (libsource (lib "easyedapro") (part "0603WAF2402T5E"))
    )
    (comp (ref "R92")
      (value "10K")
      (footprint "easyedapro:R0603")
      (description "电阻类型:厚膜电阻;阻值:24kΩ;精度:±1%;功率:100mW;工作电压:75V;温度系数:±100ppm/°C;")
      (fields
        (field (name "Manufacturer Part") "0603WAF2402T5E")
        (field (name "Manufacturer") "UNI-ROYAL(厚声)")
      )
      (libsource (lib "easyedapro") (part "0603WAF2402T5E"))
    )
    (comp (ref "R94")
      (value "10K")
      (footprint "easyedapro:R0603")
      (description "电阻类型:厚膜电阻;阻值:24kΩ;精度:±1%;功率:100mW;工作电压:75V;温度系数:±100ppm/°C;")
      (fields
        (field (name "Manufacturer Part") "0603WAF2402T5E")
        (field (name "Manufacturer") "UNI-ROYAL(厚声)")
      )
      (libsource (lib "easyedapro") (part "0603WAF2402T5E"))
    )
    (comp (ref "R95")
      (value "10K")
      (footprint "easyedapro:R0603")
      (description "电阻类型:厚膜电阻;阻值:24kΩ;精度:±1%;功率:100mW;工作电压:75V;温度系数:±100ppm/°C;")
      (fields
        (field (name "Manufacturer Part") "0603WAF2402T5E")
        (field (name "Manufacturer") "UNI-ROYAL(厚声)")
      )
      (libsource (lib "easyedapro") (part "0603WAF2402T5E"))
    )
    (comp (ref "U1")
      (value "XL1509-5.0E1")
      (footprint "easyedapro:SOIC-8_L5.0-W4.0-P1.27-LS6.0-BL")
      (description "功能类型:降压型;同步整流:-;输出通道数:-;拓扑结构:-;输入电压:-;输出电流(最大值):-;开关频率:-;")
      (fields (field (name "Manufacturer") "XLSEMI(芯龙)"))
      (libsource (lib "easyedapro") (part "XL1509-5.0E1"))
    )
    (comp (ref "U2")
      (value "1117-3.3")
      (footprint "easyedapro:SOT-223")
      (libsource (lib "easyedapro") (part "LM1117"))
    )
    (comp (ref "U3")
      (value "LTV-357T-C")
      (footprint "easyedapro:SOP-4_L4.4-W3.9-P2.54-LS7.0-TL")
      (fields (field (name "Manufacturer") "LITEON(光宝)"))
      (libsource (lib "easyedapro") (part "LTV-357T-C"))
    )
    (comp (ref "U5")
      (value "ESPS3-32-WROOM-1-N16R8")
      (footprint "easyedapro:WIRELM-SMD_ESP32-S3-WROOM-2-N32R8V")
      (description "核心处理器:ESP32-S3R8V芯片;频率:2.4GHz;发射功率:20.5dBm;")
      (fields
        (field (name "Manufacturer Part") "ESP32-S3-WROOM-2-N32R8V")
        (field (name "Manufacturer") "ESPRESSIF(乐鑫)")
      )
      (libsource (lib "easyedapro") (part "ESP32-S3-WROOM-2-N32R8V"))
    )
    (comp (ref "U7")
      (value "SP3232EEN-L/TR")
      (footprint "easyedapro:SOIC-16_L9.9-W3.9-P1.27-LS6.0-BL")
      (description "类型:收发器;数据速率:235Kbps;")
      (fields (field (name "Manufacturer") "MaxLinear(迈凌)"))
      (libsource (lib "easyedapro") (part "SP3232EEN-L/TR"))
    )
    (comp (ref "U8")
      (value "自弹TF卡座TFAA")
      (footprint "easyedapro:SIM-SMD_C9900015645")
      (libsource (lib "easyedapro") (part "自弹TF卡座TFAA"))
    )
    (comp (ref "U10")
      (value "LTV-357T-C")
      (footprint "easyedapro:SOP-4_L4.4-W3.9-P2.54-LS7.0-TL")
      (fields (field (name "Manufacturer") "LITEON(光宝)"))
      (libsource (lib "easyedapro") (part "LTV-357T-C"))
    )
    (comp (ref "U18")
      (value "LTV-357T-C")
      (footprint "easyedapro:SOP-4_L4.4-W3.9-P2.54-LS7.0-TL")
      (fields (field (name "Manufacturer") "LITEON(光宝)"))
      (libsource (lib "easyedapro") (part "LTV-357T-C"))
    )
    (comp (ref "U20")
      (value "74LVC1G17")
      (footprint "easyedapro:SMD8")
      (libsource (lib "easyedapro") (part "74LVC1G04"))
    )
    (comp (ref "U21")
      (value "LTV-357T-C")
      (footprint "easyedapro:SOP-4_L4.4-W3.9-P2.54-LS7.0-TL")
      (fields (field (name "Manufacturer") "LITEON(光宝)"))
      (libsource (lib "easyedapro") (part "LTV-357T-C"))
    )
    (comp (ref "U23")
      (value "CA-IS3760")
      (footprint "easyedapro:SOIC-16_L9.9-W3.9-P1.27-LS6.0-BL")
      (fields (field (name "Manufacturer") "Chipanalog(川土微)"))
      (libsource (lib "easyedapro") (part "CA-IS3760HN"))
    )
    (comp (ref "U24")
      (value "74LVC1G17")
      (footprint "easyedapro:SMD8")
      (libsource (lib "easyedapro") (part "74LVC1G04"))
    )
    (comp (ref "U25")
      (value "74LVC1G17")
      (footprint "easyedapro:SMD8")
      (libsource (lib "easyedapro") (part "74LVC1G04"))
    )
    (comp (ref "U26")
      (value "CH340G")
      (footprint "easyedapro:SOIC-16_L9.9-W3.9-P1.27-LS6.0-BL")
      (description "应用功能:收发器;接口协议:USB 2.0;数据速率:2Mbps;")
      (fields (field (name "Manufacturer") "WCH(南京沁恒)"))
      (libsource (lib "easyedapro") (part "CH340G"))
    )
    (comp (ref "USB1")
      (value "U-USBAR04P-F002")
      (footprint "easyedapro:USB-A-TH_USB-302-T")
      (description "连接器类型:Type-A;协议标准:USB 2.0;公母:母;安装方式:弯插;触点数量:4P;端口数量:1;额定电流 - 电源:1.5A;工作温度:0°C~+50°C;")
      (fields (field (name "Manufacturer") "Ckmtw(灿科盟)"))
      (libsource (lib "easyedapro") (part "U-USBAR04P-F001"))
    )
    (comp (ref "USB2")
      (value "TYPE-C 16PIN")
      (footprint "easyedapro:USB-C-SMD_TYPE-C-6PIN-2MD-073")
      (description "连接器类型:Type-C;标准:-;公母:母;端口数量:1;触点数量:16P;安装方式:卧贴;额定电流 - 电源:5A;工作温度范围:-25°C~+85°C;")
      (fields (field (name "Manufacturer") "SHOU HAN(首韩)"))
      (libsource (lib "easyedapro") (part "TYPE-C 16PIN 2MD(073)"))
    )
    (comp (ref "USB7")
      (value "AF 10.0 QT-ZB6.8")
      (footprint "easyedapro:USB-A-SMD_AF-10.0-QT-ZB6.8")
      (description "连接器类型:Type-A;协议标准:USB 2.0;公母:母;安装方式:卧贴;触点数量:4P;端口数量:1;额定电流 - 电源:1.5A;工作温度:-25°C~+85°C;")
      (fields (field (name "Manufacturer") "SHOU HAN(首韩)"))
      (libsource (lib "easyedapro") (part "AF 10.0 QT-ZB6.8"))
    )
    (comp (ref "USB8")
      (value "TYPE-C 16PIN(MC-107SSY)")
      (footprint "easyedapro:USB-TYPE-C-SMD_MC-107SSY")
      (description "连接器类型:Type-C;协议标准:USB 3.1;公母:母;安装方式:卧贴;触点数量:16P;端口数量:1;额定电流 - 电源:5A;工作温度:-25°C~+85°C;")
      (fields (field (name "Manufacturer") "HANBO(汉博)"))
      (libsource (lib "easyedapro") (part "MC-107SSY"))
    )
    (comp (ref "Y1")
      (value "12M")
      (footprint "easyedapro:晶振贴片49SSMD")
      (description "Crystal Oscillator")
      (libsource (lib "easyedapro") (part "XTAL"))
    )
  )
  (nets
    (net (code "1") (name "/2_EN_O") (class "Default")
      (node (ref "H10") (pin "8") (pinfunction "8_8") (pintype "unspecified"))
      (node (ref "H2") (pin "8") (pinfunction "8_8") (pintype "unspecified"))
      (node (ref "H4") (pin "8") (pinfunction "8_8") (pintype "unspecified"))
      (node (ref "H7") (pin "8") (pinfunction "8_8") (pintype "unspecified"))
    )
    (net (code "2") (name "/340_R") (class "Default")
      (node (ref "D8") (pin "2") (pinfunction "A_2") (pintype "unspecified"))
      (node (ref "R92") (pin "1") (pinfunction "1_1") (pintype "input"))
      (node (ref "U26") (pin "3") (pinfunction "RXD_3") (pintype "unspecified"))
    )
    (net (code "3") (name "/340_T") (class "Default")
      (node (ref "D9") (pin "1") (pinfunction "K_1") (pintype "unspecified"))
      (node (ref "U26") (pin "2") (pinfunction "TXD_2") (pintype "unspecified"))
    )
    (net (code "4") (name "/A_1A") (class "Default")
      (node (ref "H11") (pin "4") (pinfunction "4_4") (pintype "unspecified"))
      (node (ref "P31") (pin "3") (pinfunction "3_3") (pintype "unspecified"))
      (node (ref "R88") (pin "2") (pinfunction "2_2") (pintype "input"))
    )
    (net (code "5") (name "/A_1B") (class "Default")
      (node (ref "H11") (pin "3") (pinfunction "3_3") (pintype "unspecified"))
      (node (ref "P31") (pin "4") (pinfunction "4_4") (pintype "unspecified"))
      (node (ref "R89") (pin "2") (pinfunction "2_2") (pintype "input"))
    )
    (net (code "6") (name "/A_2A") (class "Default")
      (node (ref "H11") (pin "5") (pinfunction "5_5") (pintype "unspecified"))
      (node (ref "P31") (pin "2") (pinfunction "2_2") (pintype "unspecified"))
      (node (ref "R87") (pin "2") (pinfunction "2_2") (pintype "input"))
    )
    (net (code "7") (name "/A_2B") (class "Default")
      (node (ref "H11") (pin "6") (pinfunction "6_6") (pintype "unspecified"))
      (node (ref "P31") (pin "1") (pinfunction "1_1") (pintype "unspecified"))
      (node (ref "R86") (pin "2") (pinfunction "2_2") (pintype "input"))
    )
    (net (code "8") (name "/A_DIR_O") (class "Default")
      (node (ref "H10") (pin "1") (pinfunction "1_1") (pintype "unspecified"))
      (node (ref "H2") (pin "1") (pinfunction "1_1") (pintype "unspecified"))
    )
    (net (code "9") (name "/A_STEP_O") (class "Default")
      (node (ref "H10") (pin "2") (pinfunction "2_2") (pintype "unspecified"))
      (node (ref "H2") (pin "2") (pinfunction "2_2") (pintype "unspecified"))
      (node (ref "U23") (pin "15") (pinfunction "VO1_15") (pintype "unspecified"))
    )
    (net (code "10") (name "/B_DIR_O") (class "Default")
      (node (ref "H4") (pin "1") (pinfunction "1_1") (pintype "unspecified"))
    )
    (net (code "11") (name "/B_STEP_O") (class "Default")
      (node (ref "H4") (pin "2") (pinfunction "2_2") (pintype "unspecified"))
    )
    (net (code "12") (name "/CC1") (class "Default")
      (node (ref "USB2") (pin "4") (pinfunction "CC1_4") (pintype "unspecified"))
    )
    (net (code "13") (name "/CC2") (class "Default")
      (node (ref "USB2") (pin "10") (pinfunction "CC2_10") (pintype "unspecified"))
    )
    (net (code "14") (name "/C_1A") (class "Default")
      (node (ref "P23") (pin "3") (pinfunction "3_3") (pintype "unspecified"))
      (node (ref "R71") (pin "2") (pinfunction "2_2") (pintype "input"))
    )
    (net (code "15") (name "/C_1B") (class "Default")
      (node (ref "P23") (pin "4") (pinfunction "4_4") (pintype "unspecified"))
      (node (ref "R72") (pin "2") (pinfunction "2_2") (pintype "input"))
    )
    (net (code "16") (name "/C_2A") (class "Default")
      (node (ref "P23") (pin "2") (pinfunction "2_2") (pintype "unspecified"))
      (node (ref "R70") (pin "2") (pinfunction "2_2") (pintype "input"))
    )
    (net (code "17") (name "/C_2B") (class "Default")
      (node (ref "P23") (pin "1") (pinfunction "1_1") (pintype "unspecified"))
      (node (ref "R69") (pin "2") (pinfunction "2_2") (pintype "input"))
    )
    (net (code "18") (name "/D1+") (class "Default")
      (node (ref "D7") (pin "3") (pinfunction "I/O2_3") (pintype "unspecified"))
      (node (ref "USB1") (pin "3") (pinfunction "D+_3") (pintype "unspecified"))
      (node (ref "USB7") (pin "3") (pinfunction "D+_3") (pintype "unspecified"))
    )
    (net (code "19") (name "/D1-") (class "Default")
      (node (ref "D7") (pin "1") (pinfunction "I/O1_1") (pintype "unspecified"))
      (node (ref "USB1") (pin "2") (pinfunction "D-_2") (pintype "unspecified"))
      (node (ref "USB7") (pin "2") (pinfunction "D-_2") (pintype "unspecified"))
    )
    (net (code "20") (name "/DM") (class "Default")
      (node (ref "D24") (pin "6") (pinfunction "I/O1_6") (pintype "unspecified"))
    )
    (net (code "21") (name "/DN_D-") (class "Default")
      (node (ref "U26") (pin "6") (pinfunction "UD-_6") (pintype "unspecified"))
      (node (ref "USB2") (pin "5") (pinfunction "DN2_5") (pintype "unspecified"))
      (node (ref "USB2") (pin "7") (pinfunction "DN1_7") (pintype "unspecified"))
      (node (ref "USB8") (pin "A7") (pinfunction "DN1_A7") (pintype "unspecified"))
      (node (ref "USB8") (pin "B7") (pinfunction "DN2_B7") (pintype "unspecified"))
    )
    (net (code "22") (name "/DP") (class "Default")
      (node (ref "D24") (pin "4") (pinfunction "I/O2_4") (pintype "unspecified"))
    )
    (net (code "23") (name "/DP_D+") (class "Default")
      (node (ref "U26") (pin "5") (pinfunction "UD+_5") (pintype "unspecified"))
      (node (ref "USB2") (pin "6") (pinfunction "DP1_6") (pintype "unspecified"))
      (node (ref "USB2") (pin "8") (pinfunction "DP2_8") (pintype "unspecified"))
      (node (ref "USB8") (pin "A6") (pinfunction "DP1_A6") (pintype "unspecified"))
      (node (ref "USB8") (pin "B6") (pinfunction "DP2_B6") (pintype "unspecified"))
    )
    (net (code "24") (name "/DTR") (class "Default")
      (node (ref "Q2") (pin "2") (pinfunction "E_2") (pintype "unspecified"))
      (node (ref "R95") (pin "2") (pinfunction "2_2") (pintype "input"))
      (node (ref "U26") (pin "13") (pinfunction "DTR#_13") (pintype "unspecified"))
    )
    (net (code "25") (name "/ESP_RST") (class "Default")
      (node (ref "C48") (pin "2") (pinfunction "2_2") (pintype "input"))
      (node (ref "H1") (pin "5") (pinfunction "5_5") (pintype "unspecified"))
      (node (ref "Q3") (pin "3") (pinfunction "C_3") (pintype "unspecified"))
      (node (ref "R73") (pin "2") (pinfunction "2_2") (pintype "input"))
      (node (ref "U5") (pin "3") (pinfunction "EN_3") (pintype "unspecified"))
    )
    (net (code "26") (name "/IO0_G3") (class "Default")
      (node (ref "H1") (pin "6") (pinfunction "6_6") (pintype "unspecified"))
      (node (ref "Q2") (pin "3") (pinfunction "C_3") (pintype "unspecified"))
      (node (ref "R76") (pin "2") (pinfunction "2_2") (pintype "input"))
      (node (ref "U5") (pin "27") (pinfunction "IO0_27") (pintype "unspecified"))
    )
    (net (code "27") (name "/IO1_R3") (class "Default")
      (node (ref "U5") (pin "39") (pinfunction "IO1_39") (pintype "unspecified"))
    )
    (net (code "28") (name "/IO2_R4") (class "Default")
      (node (ref "U5") (pin "38") (pinfunction "IO2_38") (pintype "unspecified"))
    )
    (net (code "29") (name "/IO3_VSY") (class "Default")
      (node (ref "U5") (pin "15") (pinfunction "IO3_15") (pintype "unspecified"))
    )
    (net (code "30") (name "/IO4_INT") (class "Default")
      (node (ref "U5") (pin "4") (pinfunction "IO4_4") (pintype "unspecified"))
    )
    (net (code "31") (name "/IO5_DE") (class "Default")
      (node (ref "U5") (pin "5") (pinfunction "IO5_5") (pintype "unspecified"))
    )
    (net (code "32") (name "/IO6_G3") (class "Default")
      (node (ref "U5") (pin "6") (pinfunction "IO6_6") (pintype "unspecified"))
    )
    (net (code "33") (name "/IO7_PCLK") (class "Default")
      (node (ref "U5") (pin "7") (pinfunction "IO7_7") (pintype "unspecified"))
    )
    (net (code "34") (name "/IO8_SDA") (class "Default")
      (node (ref "U5") (pin "12") (pinfunction "IO8_12") (pintype "unspecified"))
    )
    (net (code "35") (name "/IO9_SCL") (class "Default")
      (node (ref "U5") (pin "17") (pinfunction "IO9_17") (pintype "unspecified"))
    )
    (net (code "36") (name "/IO10_B7") (class "Default")
      (node (ref "U5") (pin "18") (pinfunction "IO10_18") (pintype "unspecified"))
    )
    (net (code "37") (name "/IO14_B3") (class "Default")
      (node (ref "U5") (pin "22") (pinfunction "IO14_22") (pintype "unspecified"))
    )
    (net (code "38") (name "/IO17_B6") (class "Default")
      (node (ref "U5") (pin "10") (pinfunction "IO17_10") (pintype "unspecified"))
    )
    (net (code "39") (name "/IO18_B5") (class "Default")
      (node (ref "U5") (pin "11") (pinfunction "IO18_11") (pintype "unspecified"))
    )
    (net (code "40") (name "/IO21_G7") (class "Default")
      (node (ref "U5") (pin "23") (pinfunction "IO21_23") (pintype "unspecified"))
    )
    (net (code "41") (name "/IO38_B4") (class "Default")
      (node (ref "U5") (pin "31") (pinfunction "IO38_31") (pintype "unspecified"))
    )
    (net (code "42") (name "/IO39_G2") (class "Default")
      (node (ref "U5") (pin "32") (pinfunction "IO39_32") (pintype "unspecified"))
    )
    (net (code "43") (name "/IO40_R7") (class "Default")
      (node (ref "U5") (pin "33") (pinfunction "IO40_33") (pintype "unspecified"))
    )
    (net (code "44") (name "/IO41_R6") (class "Default")
      (node (ref "U5") (pin "34") (pinfunction "IO41_34") (pintype "unspecified"))
    )
    (net (code "45") (name "/IO42_R5") (class "Default")
      (node (ref "U5") (pin "35") (pinfunction "IO42_35") (pintype "unspecified"))
    )
    (net (code "46") (name "/IO45_G4") (class "Default")
      (node (ref "U5") (pin "26") (pinfunction "IO45_26") (pintype "unspecified"))
    )
    (net (code "47") (name "/IO46_HSY") (class "Default")
      (node (ref "U5") (pin "16") (pinfunction "IO46_16") (pintype "unspecified"))
    )
    (net (code "48") (name "/IO47_G6") (class "Default")
      (node (ref "U5") (pin "24") (pinfunction "IO47_24") (pintype "unspecified"))
    )
    (net (code "49") (name "/IO48_G5") (class "Default")
      (node (ref "U5") (pin "25") (pinfunction "IO48_25") (pintype "unspecified"))
    )
    (net (code "50") (name "/MA_STEP") (class "Default")
      (node (ref "U23") (pin "2") (pinfunction "VI1_2") (pintype "unspecified"))
    )
    (net (code "51") (name "/MOTOR_EN") (class "Default")
      (node (ref "R25") (pin "1") (pinfunction "1_1") (pintype "input"))
      (node (ref "U24") (pin "2") (pinfunction "A_2") (pintype "unspecified"))
    )
    (net (code "52") (name "/MX_DIR") (class "Default")
      (node (ref "R24") (pin "1") (pinfunction "1_1") (pintype "input"))
      (node (ref "U25") (pin "2") (pinfunction "A_2") (pintype "unspecified"))
    )
    (net (code "53") (name "/MX_STEP") (class "Default")
      (node (ref "U23") (pin "7") (pinfunction "VI6_7") (pintype "unspecified"))
    )
    (net (code "54") (name "/MY_DIR") (class "Default")
      (node (ref "U23") (pin "6") (pinfunction "VI5_6") (pintype "unspecified"))
    )
    (net (code "55") (name "/MY_STEP") (class "Default")
      (node (ref "U23") (pin "5") (pinfunction "VI4_5") (pintype "unspecified"))
    )
    (net (code "56") (name "/MZ_DIR") (class "Default")
      (node (ref "U23") (pin "4") (pinfunction "VI3_4") (pintype "unspecified"))
    )
    (net (code "57") (name "/MZ_STEP") (class "Default")
      (node (ref "U23") (pin "3") (pinfunction "VI2_3") (pintype "unspecified"))
    )
    (net (code "58") (name "/M_EN_O") (class "Default")
      (node (ref "U24") (pin "4") (pinfunction "Y_4") (pintype "unspecified"))
    )
    (net (code "59") (name "/PROBE") (class "Default")
      (node (ref "R78") (pin "2") (pinfunction "2_2") (pintype "input"))
      (node (ref "U18") (pin "4") (pinfunction "4_4") (pintype "unspecified"))
    )
    (net (code "60") (name "/PROBE_O") (class "Default")
      (node (ref "D26") (pin "2") (pinfunction "2_2") (pintype "input"))
      (node (ref "P22") (pin "1") (pintype "input"))
      (node (ref "U18") (pin "2") (pinfunction "2_2") (pintype "unspecified"))
    )
    (net (code "61") (name "/PWM") (class "Default")
      (node (ref "U20") (pin "2") (pinfunction "A_2") (pintype "unspecified"))
    )
    (net (code "62") (name "/PWM_5V") (class "Default")
      (node (ref "D25") (pin "2") (pinfunction "2_2") (pintype "input"))
      (node (ref "P24") (pin "1") (pinfunction "1_1") (pintype "unspecified"))
      (node (ref "P29") (pin "1") (pinfunction "1_1") (pintype "unspecified"))
      (node (ref "U20") (pin "4") (pinfunction "Y_4") (pintype "unspecified"))
    )
    (net (code "63") (name "/R1IN") (class "Default")
      (node (ref "P9") (pin "2") (pinfunction "2_2") (pintype "unspecified"))
      (node (ref "U7") (pin "13") (pinfunction "R1IN_13") (pintype "unspecified"))
    )
    (net (code "64") (name "/R1OUT") (class "Default")
      (node (ref "D12") (pin "1") (pinfunction "K_1") (pintype "unspecified"))
      (node (ref "U7") (pin "12") (pinfunction "R1OUT_12") (pintype "unspecified"))
    )
    (net (code "65") (name "/R2IN") (class "Default")
      (node (ref "P10") (pin "3") (pinfunction "3_3") (pintype "unspecified"))
      (node (ref "U7") (pin "8") (pinfunction "R2IN_8") (pintype "unspecified"))
    )
    (net (code "66") (name "/R2OUT") (class "Default")
      (node (ref "D15") (pin "1") (pinfunction "K_1") (pintype "unspecified"))
      (node (ref "U7") (pin "9") (pinfunction "R2OUT_9") (pintype "unspecified"))
    )
    (net (code "67") (name "/RTS") (class "Default")
      (node (ref "Q3") (pin "2") (pinfunction "E_2") (pintype "unspecified"))
      (node (ref "R94") (pin "2") (pinfunction "2_2") (pintype "input"))
      (node (ref "U26") (pin "14") (pinfunction "RTS#_14") (pintype "unspecified"))
    )
    (net (code "68") (name "/RXD") (class "Default")
      (node (ref "H6") (pin "2") (pinfunction "2_2") (pintype "unspecified"))
    )
    (net (code "69") (name "/RXD0") (class "Default")
      (node (ref "D15") (pin "2") (pinfunction "A_2") (pintype "unspecified"))
      (node (ref "D9") (pin "2") (pinfunction "A_2") (pintype "unspecified"))
      (node (ref "H1") (pin "4") (pinfunction "4_4") (pintype "unspecified"))
      (node (ref "H9") (pin "1") (pinfunction "1_1") (pintype "unspecified"))
      (node (ref "R91") (pin "1") (pinfunction "1_1") (pintype "input"))
      (node (ref "U5") (pin "36") (pinfunction "RXD0_36") (pintype "unspecified"))
    )
    (net (code "70") (name "/RXD1") (class "Default")
      (node (ref "D12") (pin "2") (pinfunction "A_2") (pintype "unspecified"))
      (node (ref "H9") (pin "4") (pinfunction "4_4") (pintype "unspecified"))
      (node (ref "R74") (pin "2") (pinfunction "2_2") (pintype "input"))
      (node (ref "U5") (pin "8") (pinfunction "IO15_8") (pintype "unspecified"))
    )
    (net (code "71") (name "/SD_CD") (class "Default")
      (node (ref "R30") (pin "1") (pinfunction "1_1") (pintype "unspecified"))
      (node (ref "U8") (pin "9") (pinfunction "CD_9") (pintype "unspecified"))
    )
    (net (code "72") (name "/SD_CS") (class "Default")
      (node (ref "R27") (pin "1") (pinfunction "1_1") (pintype "unspecified"))
      (node (ref "U8") (pin "2") (pinfunction "CD_2") (pintype "unspecified"))
    )
    (net (code "73") (name "/SD_MISO") (class "Default")
      (node (ref "R29") (pin "1") (pinfunction "1_1") (pintype "unspecified"))
      (node (ref "U5") (pin "21") (pinfunction "IO13_21") (pintype "unspecified"))
      (node (ref "U8") (pin "7") (pinfunction "DAT0_7") (pintype "unspecified"))
    )
    (net (code "74") (name "/SD_MOSI") (class "Default")
      (node (ref "R28") (pin "1") (pinfunction "1_1") (pintype "unspecified"))
      (node (ref "U5") (pin "19") (pinfunction "IO11_19") (pintype "unspecified"))
      (node (ref "U8") (pin "3") (pinfunction "CMD_3") (pintype "unspecified"))
    )
    (net (code "75") (name "/SD_SCLK") (class "Default")
      (node (ref "U5") (pin "20") (pinfunction "IO12_20") (pintype "unspecified"))
      (node (ref "U8") (pin "5") (pinfunction "CLX_5") (pintype "unspecified"))
    )
    (net (code "76") (name "/SL_D+") (class "Default")
      (node (ref "D24") (pin "3") (pinfunction "I/O2_3") (pintype "unspecified"))
    )
    (net (code "77") (name "/SL_D-") (class "Default")
      (node (ref "D24") (pin "1") (pinfunction "I/O1_1") (pintype "unspecified"))
    )
    (net (code "78") (name "/T1IN") (class "Default")
      (node (ref "D13") (pin "2") (pinfunction "A_2") (pintype "unspecified"))
      (node (ref "R34") (pin "2") (pinfunction "2_2") (pintype "unspecified"))
      (node (ref "U7") (pin "11") (pinfunction "T1IN_11") (pintype "unspecified"))
    )
    (net (code "79") (name "/T1OUT") (class "Default")
      (node (ref "P9") (pin "3") (pinfunction "3_3") (pintype "unspecified"))
      (node (ref "U7") (pin "14") (pinfunction "T1OUT_14") (pintype "unspecified"))
    )
    (net (code "80") (name "/T2IN") (class "Default")
      (node (ref "D14") (pin "2") (pinfunction "A_2") (pintype "unspecified"))
      (node (ref "R35") (pin "2") (pinfunction "2_2") (pintype "unspecified"))
      (node (ref "U7") (pin "10") (pinfunction "T2IN_10") (pintype "unspecified"))
    )
    (net (code "81") (name "/T2OUT") (class "Default")
      (node (ref "P10") (pin "2") (pinfunction "2_2") (pintype "unspecified"))
      (node (ref "U7") (pin "7") (pinfunction "T2OUT_7") (pintype "unspecified"))
    )
    (net (code "82") (name "/TXD") (class "Default")
      (node (ref "H6") (pin "1") (pinfunction "1_1") (pintype "unspecified"))
    )
    (net (code "83") (name "/TXD0") (class "Default")
      (node (ref "D14") (pin "1") (pinfunction "K_1") (pintype "unspecified"))
      (node (ref "D8") (pin "1") (pinfunction "K_1") (pintype "unspecified"))
      (node (ref "H1") (pin "3") (pinfunction "3_3") (pintype "unspecified"))
      (node (ref "H9") (pin "2") (pinfunction "2_2") (pintype "unspecified"))
      (node (ref "U5") (pin "37") (pinfunction "TXD0_37") (pintype "unspecified"))
    )
    (net (code "84") (name "/TXD1") (class "Default")
      (node (ref "D13") (pin "1") (pinfunction "K_1") (pintype "unspecified"))
      (node (ref "H9") (pin "3") (pinfunction "3_3") (pintype "unspecified"))
      (node (ref "U5") (pin "9") (pinfunction "IO16_9") (pintype "unspecified"))
    )
    (net (code "85") (name "/USB_D+") (class "Default")
      (node (ref "D7") (pin "4") (pinfunction "I/O2_4") (pintype "unspecified"))
      (node (ref "U5") (pin "14") (pinfunction "IO20_14") (pintype "unspecified"))
    )
    (net (code "86") (name "/USB_D-") (class "Default")
      (node (ref "D7") (pin "6") (pinfunction "I/O1_6") (pintype "unspecified"))
      (node (ref "U5") (pin "13") (pinfunction "IO19_13") (pintype "unspecified"))
    )
    (net (code "87") (name "/VUSB") (class "Default")
      (node (ref "D24") (pin "5") (pinfunction "VBUS_5") (pintype "unspecified"))
    )
    (net (code "88") (name "/X_1A") (class "Default")
      (node (ref "H3") (pin "4") (pinfunction "4_4") (pintype "unspecified"))
      (node (ref "P18") (pin "3") (pinfunction "3_3") (pintype "unspecified"))
      (node (ref "R63") (pin "2") (pinfunction "2_2") (pintype "input"))
    )
    (net (code "89") (name "/X_1B") (class "Default")
      (node (ref "H3") (pin "3") (pinfunction "3_3") (pintype "unspecified"))
      (node (ref "P18") (pin "4") (pinfunction "4_4") (pintype "unspecified"))
      (node (ref "R64") (pin "2") (pinfunction "2_2") (pintype "input"))
    )
    (net (code "90") (name "/X_2A") (class "Default")
      (node (ref "H3") (pin "5") (pinfunction "5_5") (pintype "unspecified"))
      (node (ref "P18") (pin "2") (pinfunction "2_2") (pintype "unspecified"))
      (node (ref "R62") (pin "2") (pinfunction "2_2") (pintype "input"))
    )
    (net (code "91") (name "/X_2B") (class "Default")
      (node (ref "H3") (pin "6") (pinfunction "6_6") (pintype "unspecified"))
      (node (ref "P18") (pin "1") (pinfunction "1_1") (pintype "unspecified"))
      (node (ref "R61") (pin "2") (pinfunction "2_2") (pintype "input"))
    )
    (net (code "92") (name "/X_DIR_O") (class "Default")
      (node (ref "U25") (pin "4") (pinfunction "Y_4") (pintype "unspecified"))
    )
    (net (code "93") (name "/X_LIMT") (class "Default")
      (node (ref "R85") (pin "2") (pinfunction "2_2") (pintype "input"))
      (node (ref "U3") (pin "4") (pinfunction "4_4") (pintype "unspecified"))
    )
    (net (code "94") (name "/X_LIMT_I") (class "Default")
      (node (ref "P30") (pin "1") (pinfunction "1_1") (pintype "unspecified"))
      (node (ref "P8") (pin "1") (pinfunction "1_1") (pintype "unspecified"))
      (node (ref "U3") (pin "2") (pinfunction "2_2") (pintype "unspecified"))
    )
    (net (code "95") (name "/X_STEP_O") (class "Default")
      (node (ref "U23") (pin "10") (pinfunction "VO6_10") (pintype "unspecified"))
    )
    (net (code "96") (name "/Y_1A") (class "Default")
      (node (ref "H5") (pin "4") (pinfunction "4_4") (pintype "unspecified"))
      (node (ref "P21") (pin "3") (pinfunction "3_3") (pintype "unspecified"))
      (node (ref "R67") (pin "2") (pinfunction "2_2") (pintype "input"))
    )
    (net (code "97") (name "/Y_1B") (class "Default")
      (node (ref "H5") (pin "3") (pinfunction "3_3") (pintype "unspecified"))
      (node (ref "P21") (pin "4") (pinfunction "4_4") (pintype "unspecified"))
      (node (ref "R68") (pin "2") (pinfunction "2_2") (pintype "input"))
    )
    (net (code "98") (name "/Y_2A") (class "Default")
      (node (ref "H5") (pin "5") (pinfunction "5_5") (pintype "unspecified"))
      (node (ref "P21") (pin "2") (pinfunction "2_2") (pintype "unspecified"))
      (node (ref "R66") (pin "2") (pinfunction "2_2") (pintype "input"))
    )
    (net (code "99") (name "/Y_2B") (class "Default")
      (node (ref "H5") (pin "6") (pinfunction "6_6") (pintype "unspecified"))
      (node (ref "P21") (pin "1") (pinfunction "1_1") (pintype "unspecified"))
      (node (ref "R65") (pin "2") (pinfunction "2_2") (pintype "input"))
    )
    (net (code "100") (name "/Y_DIR_O") (class "Default")
      (node (ref "U23") (pin "11") (pinfunction "VO5_11") (pintype "unspecified"))
    )
    (net (code "101") (name "/Y_LIMT") (class "Default")
      (node (ref "R84") (pin "2") (pinfunction "2_2") (pintype "input"))
      (node (ref "U21") (pin "4") (pinfunction "4_4") (pintype "unspecified"))
    )
    (net (code "102") (name "/Y_LIMT_I") (class "Default")
      (node (ref "P11") (pin "1") (pinfunction "1_1") (pintype "unspecified"))
      (node (ref "P12") (pin "1") (pinfunction "1_1") (pintype "unspecified"))
      (node (ref "U21") (pin "2") (pinfunction "2_2") (pintype "unspecified"))
    )
    (net (code "103") (name "/Y_STEP_O") (class "Default")
      (node (ref "U23") (pin "12") (pinfunction "VO4_12") (pintype "unspecified"))
    )
    (net (code "104") (name "/Z_1A") (class "Default")
      (node (ref "H8") (pin "4") (pinfunction "4_4") (pintype "unspecified"))
    )
    (net (code "105") (name "/Z_1B") (class "Default")
      (node (ref "H8") (pin "3") (pinfunction "3_3") (pintype "unspecified"))
    )
    (net (code "106") (name "/Z_2A") (class "Default")
      (node (ref "H8") (pin "5") (pinfunction "5_5") (pintype "unspecified"))
    )
    (net (code "107") (name "/Z_2B") (class "Default")
      (node (ref "H8") (pin "6") (pinfunction "6_6") (pintype "unspecified"))
    )
    (net (code "108") (name "/Z_DIR_O") (class "Default")
      (node (ref "H7") (pin "1") (pinfunction "1_1") (pintype "unspecified"))
      (node (ref "U23") (pin "13") (pinfunction "VO3_13") (pintype "unspecified"))
    )
    (net (code "109") (name "/Z_LIMT") (class "Default")
      (node (ref "R83") (pin "2") (pinfunction "2_2") (pintype "input"))
      (node (ref "U10") (pin "4") (pinfunction "4_4") (pintype "unspecified"))
    )
    (net (code "110") (name "/Z_LIMT_I") (class "Default")
      (node (ref "P14") (pin "1") (pinfunction "1_1") (pintype "unspecified"))
      (node (ref "P16") (pin "1") (pinfunction "1_1") (pintype "unspecified"))
      (node (ref "U10") (pin "2") (pinfunction "2_2") (pintype "unspecified"))
    )
    (net (code "111") (name "/Z_STEP_O") (class "Default")
      (node (ref "H7") (pin "2") (pinfunction "2_2") (pintype "unspecified"))
      (node (ref "U23") (pin "14") (pinfunction "VO2_14") (pintype "unspecified"))
    )
    (net (code "112") (name "3V3") (class "Default")
      (node (ref "C27") (pin "2") (pinfunction "2_2") (pintype "unspecified"))
      (node (ref "C47") (pin "2") (pinfunction "2_2") (pintype "input"))
      (node (ref "C50") (pin "2") (pinfunction "2_2") (pintype "input"))
      (node (ref "C51") (pin "1") (pinfunction "1_1") (pintype "input"))
      (node (ref "R27") (pin "2") (pinfunction "2_2") (pintype "unspecified"))
      (node (ref "R28") (pin "2") (pinfunction "2_2") (pintype "unspecified"))
      (node (ref "R29") (pin "2") (pinfunction "2_2") (pintype "unspecified"))
      (node (ref "R30") (pin "2") (pinfunction "2_2") (pintype "unspecified"))
      (node (ref "R73") (pin "1") (pinfunction "1_1") (pintype "input"))
      (node (ref "R74") (pin "1") (pinfunction "1_1") (pintype "input"))
      (node (ref "R76") (pin "1") (pinfunction "1_1") (pintype "input"))
      (node (ref "R78") (pin "1") (pinfunction "1_1") (pintype "input"))
      (node (ref "R83") (pin "1") (pinfunction "1_1") (pintype "input"))
      (node (ref "R84") (pin "1") (pinfunction "1_1") (pintype "input"))
      (node (ref "R85") (pin "1") (pinfunction "1_1") (pintype "input"))
      (node (ref "R91") (pin "2") (pinfunction "2_2") (pintype "input"))
      (node (ref "U2") (pin "2") (pinfunction "OUT_2") (pintype "unspecified"))
      (node (ref "U2") (pin "4") (pinfunction "=_4") (pintype "unspecified"))
      (node (ref "U23") (pin "1") (pinfunction "VDDA_1") (pintype "unspecified"))
      (node (ref "U5") (pin "2") (pinfunction "3V3_2") (pintype "unspecified"))
      (node (ref "U8") (pin "4") (pinfunction "VDD_4") (pintype "unspecified"))
    )
    (net (code "113") (name "5V_2") (class "Default")
      (node (ref "H10") (pin "5") (pinfunction "5_5") (pintype "unspecified"))
      (node (ref "H10") (pin "6") (pinfunction "6_6") (pintype "unspecified"))
      (node (ref "H10") (pin "7") (pinfunction "7_7") (pintype "unspecified"))
      (node (ref "H11") (pin "2") (pinfunction "2_2") (pintype "unspecified"))
      (node (ref "H2") (pin "5") (pinfunction "5_5") (pintype "unspecified"))
      (node (ref "H2") (pin "6") (pinfunction "6_6") (pintype "unspecified"))
      (node (ref "H2") (pin "7") (pinfunction "7_7") (pintype "unspecified"))
      (node (ref "H3") (pin "2") (pinfunction "2_2") (pintype "unspecified"))
      (node (ref "H4") (pin "5") (pinfunction "5_5") (pintype "unspecified"))
      (node (ref "H4") (pin "6") (pinfunction "6_6") (pintype "unspecified"))
      (node (ref "H4") (pin "7") (pinfunction "7_7") (pintype "unspecified"))
      (node (ref "H5") (pin "2") (pinfunction "2_2") (pintype "unspecified"))
      (node (ref "H7") (pin "5") (pinfunction "5_5") (pintype "unspecified"))
      (node (ref "H7") (pin "6") (pinfunction "6_6") (pintype "unspecified"))
      (node (ref "H7") (pin "7") (pinfunction "7_7") (pintype "unspecified"))
      (node (ref "H8") (pin "2") (pinfunction "2_2") (pintype "unspecified"))
    )
    (net (code "114") (name "5V_USB") (class "Default")
      (node (ref "R21") (pin "1") (pinfunction "1_1") (pintype "unspecified"))
      (node (ref "R90") (pin "1") (pinfunction "1_1") (pintype "input"))
      (node (ref "USB2") (pin "11") (pinfunction "VBUS_11") (pintype "unspecified"))
      (node (ref "USB2") (pin "2") (pinfunction "VBUS_2") (pintype "unspecified"))
    )
    (net (code "115") (name "5V_VCC") (class "Default")
      (node (ref "C24") (pin "2") (pinfunction "2_2") (pintype "unspecified"))
      (node (ref "C35") (pin "2") (pinfunction "2_2") (pintype "unspecified"))
      (node (ref "C39") (pin "2") (pinfunction "2_2") (pintype "unspecified"))
      (node (ref "C41") (pin "2") (pinfunction "2_2") (pintype "unspecified"))
      (node (ref "C42") (pin "2") (pinfunction "2_2") (pintype "unspecified"))
      (node (ref "C43") (pin "2") (pinfunction "2_2") (pintype "unspecified"))
      (node (ref "C54") (pin "1") (pinfunction "1_1") (pintype "input"))
      (node (ref "C7") (pin "1") (pinfunction "1_1") (pintype "input"))
      (node (ref "C8") (pin "1") (pinfunction "1_1") (pintype "input"))
      (node (ref "D4") (pin "2") (pinfunction "2_2") (pintype "input"))
      (node (ref "D7") (pin "5") (pinfunction "VBUS_5") (pintype "unspecified"))
      (node (ref "H1") (pin "1") (pinfunction "1_1") (pintype "unspecified"))
      (node (ref "L1") (pin "1") (pinfunction "1_1") (pintype "unspecified"))
      (node (ref "P10") (pin "1") (pinfunction "1_1") (pintype "unspecified"))
      (node (ref "R34") (pin "1") (pinfunction "1_1") (pintype "unspecified"))
      (node (ref "R35") (pin "1") (pinfunction "1_1") (pintype "unspecified"))
      (node (ref "R58") (pin "2") (pinfunction "2_2") (pintype "input"))
      (node (ref "R77") (pin "1") (pinfunction "1_1") (pintype "input"))
      (node (ref "R90") (pin "2") (pinfunction "2_2") (pintype "input"))
      (node (ref "R92") (pin "2") (pinfunction "2_2") (pintype "input"))
      (node (ref "U1") (pin "3") (pinfunction "FB_3") (pintype "input"))
      (node (ref "U2") (pin "3") (pinfunction "IN_3") (pintype "unspecified"))
      (node (ref "U20") (pin "5") (pinfunction "VCC_5") (pintype "unspecified"))
      (node (ref "U23") (pin "16") (pinfunction "VDDB_16") (pintype "unspecified"))
      (node (ref "U24") (pin "5") (pinfunction "VCC_5") (pintype "unspecified"))
      (node (ref "U25") (pin "5") (pinfunction "VCC_5") (pintype "unspecified"))
      (node (ref "U26") (pin "16") (pinfunction "VCC_16") (pintype "unspecified"))
      (node (ref "U7") (pin "16") (pinfunction "VCC_16") (pintype "unspecified"))
      (node (ref "USB1") (pin "1") (pinfunction "VCC_1") (pintype "unspecified"))
      (node (ref "USB7") (pin "1") (pinfunction "VCC_1") (pintype "unspecified"))
    )
    (net (code "116") (name "24V_D1") (class "Default")
      (node (ref "C1") (pin "1") (pintype "unspecified"))
      (node (ref "C38") (pin "1") (pinfunction "1_1") (pintype "unspecified"))
      (node (ref "D1") (pin "1") (pinfunction "1_1") (pintype "unspecified"))
      (node (ref "P11") (pin "2") (pinfunction "2_2") (pintype "unspecified"))
      (node (ref "P12") (pin "2") (pinfunction "2_2") (pintype "unspecified"))
      (node (ref "P14") (pin "2") (pinfunction "2_2") (pintype "unspecified"))
      (node (ref "P16") (pin "2") (pinfunction "2_2") (pintype "unspecified"))
      (node (ref "P24") (pin "2") (pinfunction "2_2") (pintype "unspecified"))
      (node (ref "P30") (pin "2") (pinfunction "2_2") (pintype "unspecified"))
      (node (ref "P8") (pin "2") (pinfunction "2_2") (pintype "unspecified"))
      (node (ref "R60") (pin "2") (pinfunction "2_2") (pintype "input"))
      (node (ref "R79") (pin "1") (pinfunction "1_1") (pintype "input"))
      (node (ref "R81") (pin "1") (pinfunction "1_1") (pintype "input"))
      (node (ref "R82") (pin "1") (pinfunction "1_1") (pintype "input"))
      (node (ref "U1") (pin "1") (pinfunction "VIN_1") (pintype "input"))
    )
    (net (code "117") (name "24V_D2") (class "Default")
      (node (ref "C19") (pin "1") (pintype "unspecified"))
      (node (ref "C32") (pin "1") (pintype "unspecified"))
      (node (ref "C34") (pin "1") (pintype "unspecified"))
      (node (ref "C40") (pin "1") (pintype "unspecified"))
      (node (ref "D2") (pin "1") (pinfunction "1_1") (pintype "unspecified"))
      (node (ref "H11") (pin "8") (pinfunction "8_8") (pintype "unspecified"))
      (node (ref "H3") (pin "8") (pinfunction "8_8") (pintype "unspecified"))
      (node (ref "H5") (pin "8") (pinfunction "8_8") (pintype "unspecified"))
      (node (ref "H8") (pin "8") (pinfunction "8_8") (pintype "unspecified"))
    )
    (net (code "118") (name "GND") (class "Default")
      (node (ref "C1") (pin "2") (pintype "unspecified"))
      (node (ref "C19") (pin "2") (pintype "unspecified"))
      (node (ref "C22") (pin "1") (pinfunction "1_1") (pintype "unspecified"))
      (node (ref "C24") (pin "1") (pinfunction "1_1") (pintype "unspecified"))
      (node (ref "C26") (pin "2") (pinfunction "2_2") (pintype "unspecified"))
      (node (ref "C27") (pin "1") (pinfunction "1_1") (pintype "unspecified"))
      (node (ref "C32") (pin "2") (pintype "unspecified"))
      (node (ref "C34") (pin "2") (pintype "unspecified"))
      (node (ref "C35") (pin "1") (pinfunction "1_1") (pintype "unspecified"))
      (node (ref "C36") (pin "1") (pinfunction "1_1") (pintype "input"))
      (node (ref "C38") (pin "2") (pinfunction "2_2") (pintype "unspecified"))
      (node (ref "C39") (pin "1") (pinfunction "1_1") (pintype "unspecified"))
      (node (ref "C40") (pin "2") (pintype "unspecified"))
      (node (ref "C41") (pin "1") (pinfunction "1_1") (pintype "unspecified"))
      (node (ref "C42") (pin "1") (pinfunction "1_1") (pintype "unspecified"))
      (node (ref "C43") (pin "1") (pinfunction "1_1") (pintype "unspecified"))
      (node (ref "C47") (pin "1") (pinfunction "1_1") (pintype "input"))
      (node (ref "C48") (pin "1") (pinfunction "1_1") (pintype "input"))
      (node (ref "C50") (pin "1") (pinfunction "1_1") (pintype "input"))
      (node (ref "C51") (pin "2") (pinfunction "2_2") (pintype "input"))
      (node (ref "C54") (pin "2") (pinfunction "2_2") (pintype "input"))
      (node (ref "C55") (pin "2") (pinfunction "2_2") (pintype "input"))
      (node (ref "C56") (pin "1") (pinfunction "1_1") (pintype "input"))
      (node (ref "C7") (pin "2") (pinfunction "2_2") (pintype "input"))
      (node (ref "C8") (pin "2") (pinfunction "2_2") (pintype "input"))
      (node (ref "D24") (pin "2") (pinfunction "GND_2") (pintype "unspecified"))
      (node (ref "D25") (pin "1") (pinfunction "1_1") (pintype "input"))
      (node (ref "D26") (pin "1") (pinfunction "1_1") (pintype "input"))
      (node (ref "D29") (pin "2") (pinfunction "2_2") (pintype "unspecified"))
      (node (ref "D4") (pin "1") (pinfunction "1_1") (pintype "input"))
      (node (ref "D7") (pin "2") (pinfunction "GND_2") (pintype "unspecified"))
      (node (ref "DC1") (pin "2") (pinfunction "2_2") (pintype "unspecified"))
      (node (ref "DC1") (pin "3") (pinfunction "3_3") (pintype "unspecified"))
      (node (ref "H1") (pin "2") (pinfunction "2_2") (pintype "unspecified"))
      (node (ref "H11") (pin "1") (pinfunction "1_1") (pintype "unspecified"))
      (node (ref "H11") (pin "7") (pinfunction "7_7") (pintype "unspecified"))
      (node (ref "H3") (pin "1") (pinfunction "1_1") (pintype "unspecified"))
      (node (ref "H3") (pin "7") (pinfunction "7_7") (pintype "unspecified"))
      (node (ref "H5") (pin "1") (pinfunction "1_1") (pintype "unspecified"))
      (node (ref "H5") (pin "7") (pinfunction "7_7") (pintype "unspecified"))
      (node (ref "H8") (pin "1") (pinfunction "1_1") (pintype "unspecified"))
      (node (ref "H8") (pin "7") (pinfunction "7_7") (pintype "unspecified"))
      (node (ref "LED2") (pin "1") (pinfunction "K_1") (pintype "unspecified"))
      (node (ref "LED3") (pin "1") (pinfunction "K_1") (pintype "unspecified"))
      (node (ref "LED5") (pin "1") (pinfunction "K_1") (pintype "unspecified"))
      (node (ref "P10") (pin "4") (pinfunction "4_4") (pintype "unspecified"))
      (node (ref "P10") (pin "5") (pinfunction "5_5") (pintype "unspecified"))
      (node (ref "P10") (pin "6") (pinfunction "6_6") (pintype "unspecified"))
      (node (ref "P11") (pin "3") (pinfunction "3_3") (pintype "unspecified"))
      (node (ref "P12") (pin "3") (pinfunction "3_3") (pintype "unspecified"))
      (node (ref "P14") (pin "3") (pinfunction "3_3") (pintype "unspecified"))
      (node (ref "P16") (pin "3") (pinfunction "3_3") (pintype "unspecified"))
      (node (ref "P22") (pin "2") (pintype "input"))
      (node (ref "P24") (pin "3") (pinfunction "3_3") (pintype "unspecified"))
      (node (ref "P29") (pin "3") (pinfunction "3_3") (pintype "unspecified"))
      (node (ref "P30") (pin "3") (pinfunction "3_3") (pintype "unspecified"))
      (node (ref "P8") (pin "3") (pinfunction "3_3") (pintype "unspecified"))
      (node (ref "P9") (pin "4") (pinfunction "4_4") (pintype "unspecified"))
      (node (ref "P9") (pin "5") (pinfunction "5_5") (pintype "unspecified"))
      (node (ref "P9") (pin "6") (pinfunction "6_6") (pintype "unspecified"))
      (node (ref "R24") (pin "2") (pinfunction "2_2") (pintype "input"))
      (node (ref "R25") (pin "2") (pinfunction "2_2") (pintype "input"))
      (node (ref "R59") (pin "1") (pinfunction "1_1") (pintype "input"))
      (node (ref "R61") (pin "1") (pinfunction "1_1") (pintype "input"))
      (node (ref "R62") (pin "1") (pinfunction "1_1") (pintype "input"))
      (node (ref "R63") (pin "1") (pinfunction "1_1") (pintype "input"))
      (node (ref "R64") (pin "1") (pinfunction "1_1") (pintype "input"))
      (node (ref "R65") (pin "1") (pinfunction "1_1") (pintype "input"))
      (node (ref "R66") (pin "1") (pinfunction "1_1") (pintype "input"))
      (node (ref "R67") (pin "1") (pinfunction "1_1") (pintype "input"))
      (node (ref "R68") (pin "1") (pinfunction "1_1") (pintype "input"))
      (node (ref "R69") (pin "1") (pinfunction "1_1") (pintype "input"))
      (node (ref "R70") (pin "1") (pinfunction "1_1") (pintype "input"))
      (node (ref "R71") (pin "1") (pinfunction "1_1") (pintype "input"))
      (node (ref "R72") (pin "1") (pinfunction "1_1") (pintype "input"))
      (node (ref "R86") (pin "1") (pinfunction "1_1") (pintype "input"))
      (node (ref "R87") (pin "1") (pinfunction "1_1") (pintype "input"))
      (node (ref "R88") (pin "1") (pinfunction "1_1") (pintype "input"))
      (node (ref "R89") (pin "1") (pinfunction "1_1") (pintype "input"))
      (node (ref "U1") (pin "5") (pinfunction "GND_5") (pintype "input"))
      (node (ref "U1") (pin "6") (pinfunction "GND_6") (pintype "input"))
      (node (ref "U1") (pin "7") (pinfunction "GND_7") (pintype "input"))
      (node (ref "U1") (pin "8") (pinfunction "GND_8") (pintype "input"))
      (node (ref "U10") (pin "3") (pinfunction "3_3") (pintype "unspecified"))
      (node (ref "U18") (pin "3") (pinfunction "3_3") (pintype "unspecified"))
      (node (ref "U2") (pin "1") (pinfunction "GND_1") (pintype "unspecified"))
      (node (ref "U20") (pin "3") (pinfunction "GND_3") (pintype "unspecified"))
      (node (ref "U21") (pin "3") (pinfunction "3_3") (pintype "unspecified"))
      (node (ref "U23") (pin "8") (pinfunction "GNDA_8") (pintype "unspecified"))
      (node (ref "U23") (pin "9") (pinfunction "GNDB_9") (pintype "unspecified"))
      (node (ref "U24") (pin "3") (pinfunction "GND_3") (pintype "unspecified"))
      (node (ref "U25") (pin "3") (pinfunction "GND_3") (pintype "unspecified"))
      (node (ref "U26") (pin "1") (pinfunction "GND_1") (pintype "unspecified"))
      (node (ref "U3") (pin "3") (pinfunction "3_3") (pintype "unspecified"))
      (node (ref "U5") (pin "1") (pinfunction "GND_1") (pintype "unspecified"))
      (node (ref "U5") (pin "40") (pinfunction "GND_40") (pintype "unspecified"))
      (node (ref "U5") (pin "41") (pinfunction "GND_41") (pintype "unspecified"))
      (node (ref "U7") (pin "15") (pinfunction "GND_15") (pintype "unspecified"))
      (node (ref "U8") (pin "10") (pinfunction "GND_10") (pintype "unspecified"))
      (node (ref "U8") (pin "11") (pinfunction "GND_11") (pintype "unspecified"))
      (node (ref "U8") (pin "12") (pinfunction "GND_12") (pintype "unspecified"))
      (node (ref "U8") (pin "13") (pinfunction "GND_13") (pintype "unspecified"))
      (node (ref "U8") (pin "6") (pinfunction "VSS_6") (pintype "unspecified"))
      (node (ref "USB1") (pin "4") (pinfunction "GND_4") (pintype "unspecified"))
      (node (ref "USB1") (pin "5") (pinfunction "SH1_5") (pintype "unspecified"))
      (node (ref "USB1") (pin "6") (pinfunction "SH2_6") (pintype "unspecified"))
      (node (ref "USB2") (pin "1") (pinfunction "GND_1") (pintype "unspecified"))
      (node (ref "USB2") (pin "12") (pinfunction "GND_12") (pintype "unspecified"))
      (node (ref "USB2") (pin "13") (pinfunction "SHELL_13") (pintype "unspecified"))
      (node (ref "USB2") (pin "14") (pinfunction "SHELL_14") (pintype "unspecified"))
      (node (ref "USB7") (pin "4") (pinfunction "GND_4") (pintype "unspecified"))
      (node (ref "USB7") (pin "5") (pinfunction "EH_5") (pintype "unspecified"))
    )
    (net (code "119") (name "Net-(H2-Pad3)") (class "Default")
      (node (ref "H2") (pin "3") (pinfunction "3_3") (pintype "unspecified"))
      (node (ref "H2") (pin "4") (pinfunction "4_4") (pintype "unspecified"))
    )
    (net (code "120") (name "Net-(H4-Pad3)") (class "Default")
      (node (ref "H4") (pin "3") (pinfunction "3_3") (pintype "unspecified"))
      (node (ref "H4") (pin "4") (pinfunction "4_4") (pintype "unspecified"))
    )
    (net (code "121") (name "Net-(H7-Pad3)") (class "Default")
      (node (ref "H7") (pin "3") (pinfunction "3_3") (pintype "unspecified"))
      (node (ref "H7") (pin "4") (pinfunction "4_4") (pintype "unspecified"))
    )
    (net (code "122") (name "Net-(H10-Pad3)") (class "Default")
      (node (ref "H10") (pin "3") (pinfunction "3_3") (pintype "unspecified"))
      (node (ref "H10") (pin "4") (pinfunction "4_4") (pintype "unspecified"))
    )
    (net (code "123") (name "Net-(LED2-A)") (class "Default")
      (node (ref "LED2") (pin "2") (pinfunction "A_2") (pintype "unspecified"))
      (node (ref "R58") (pin "1") (pinfunction "1_1") (pintype "input"))
    )
    (net (code "124") (name "Net-(LED3-A)") (class "Default")
      (node (ref "LED3") (pin "2") (pinfunction "A_2") (pintype "unspecified"))
      (node (ref "R60") (pin "1") (pinfunction "1_1") (pintype "input"))
    )
    (net (code "125") (name "Net-(LED5-A)") (class "Default")
      (node (ref "LED5") (pin "2") (pinfunction "A_2") (pintype "unspecified"))
      (node (ref "R21") (pin "2") (pinfunction "2_2") (pintype "unspecified"))
    )
    (net (code "126") (name "Net-(Q2-B)") (class "Default")
      (node (ref "Q2") (pin "1") (pinfunction "B_1") (pintype "unspecified"))
      (node (ref "R94") (pin "1") (pinfunction "1_1") (pintype "input"))
    )
    (net (code "127") (name "Net-(Q3-B)") (class "Default")
      (node (ref "Q3") (pin "1") (pinfunction "B_1") (pintype "unspecified"))
      (node (ref "R95") (pin "1") (pinfunction "1_1") (pintype "input"))
    )
    (net (code "128") (name "Net-(R77-Pad2)") (class "Default")
      (node (ref "R77") (pin "2") (pinfunction "2_2") (pintype "input"))
      (node (ref "U18") (pin "1") (pinfunction "1_1") (pintype "unspecified"))
    )
    (net (code "129") (name "Net-(R79-Pad2)") (class "Default")
      (node (ref "R79") (pin "2") (pinfunction "2_2") (pintype "input"))
      (node (ref "U10") (pin "1") (pinfunction "1_1") (pintype "unspecified"))
    )
    (net (code "130") (name "Net-(R81-Pad2)") (class "Default")
      (node (ref "R81") (pin "2") (pinfunction "2_2") (pintype "input"))
      (node (ref "U21") (pin "1") (pinfunction "1_1") (pintype "unspecified"))
    )
    (net (code "131") (name "Net-(R82-Pad2)") (class "Default")
      (node (ref "R82") (pin "2") (pinfunction "2_2") (pintype "input"))
      (node (ref "U3") (pin "1") (pinfunction "1_1") (pintype "unspecified"))
    )
    (net (code "132") (name "Net-(U1-ON{slash}OFF)") (class "Default")
      (node (ref "R59") (pin "2") (pinfunction "2_2") (pintype "input"))
      (node (ref "U1") (pin "4") (pinfunction "ON/OFF_4") (pintype "input"))
    )
    (net (code "133") (name "Net-(U1-OUTPUT)") (class "Default")
      (node (ref "D29") (pin "1") (pinfunction "1_1") (pintype "unspecified"))
      (node (ref "L1") (pin "2") (pinfunction "2_2") (pintype "unspecified"))
      (node (ref "U1") (pin "2") (pinfunction "OUTPUT_2") (pintype "input"))
    )
    (net (code "134") (name "Net-(U7-C1+)") (class "Default")
      (node (ref "C23") (pin "2") (pinfunction "2_2") (pintype "unspecified"))
      (node (ref "U7") (pin "1") (pinfunction "C1+_1") (pintype "unspecified"))
    )
    (net (code "135") (name "Net-(U7-C1-)") (class "Default")
      (node (ref "C23") (pin "1") (pinfunction "1_1") (pintype "unspecified"))
      (node (ref "U7") (pin "3") (pinfunction "C1-_3") (pintype "unspecified"))
    )
    (net (code "136") (name "Net-(U7-C2+)") (class "Default")
      (node (ref "C25") (pin "2") (pinfunction "2_2") (pintype "unspecified"))
      (node (ref "U7") (pin "4") (pinfunction "C2+_4") (pintype "unspecified"))
    )
    (net (code "137") (name "Net-(U7-C2-)") (class "Default")
      (node (ref "C25") (pin "1") (pinfunction "1_1") (pintype "unspecified"))
      (node (ref "U7") (pin "5") (pinfunction "C2-_5") (pintype "unspecified"))
    )
    (net (code "138") (name "Net-(U7-V+)") (class "Default")
      (node (ref "C22") (pin "2") (pinfunction "2_2") (pintype "unspecified"))
      (node (ref "U7") (pin "2") (pinfunction "V+_2") (pintype "unspecified"))
    )
    (net (code "139") (name "Net-(U7-V-)") (class "Default")
      (node (ref "C26") (pin "1") (pinfunction "1_1") (pintype "unspecified"))
      (node (ref "U7") (pin "6") (pinfunction "V-_6") (pintype "unspecified"))
    )
    (net (code "140") (name "Net-(U26-V3)") (class "Default")
      (node (ref "C55") (pin "1") (pinfunction "1_1") (pintype "input"))
      (node (ref "U26") (pin "4") (pinfunction "V3_4") (pintype "unspecified"))
    )
    (net (code "141") (name "Net-(U26-XI)") (class "Default")
      (node (ref "C36") (pin "2") (pinfunction "2_2") (pintype "input"))
      (node (ref "U26") (pin "7") (pinfunction "XI_7") (pintype "unspecified"))
      (node (ref "Y1") (pin "2") (pinfunction "OSC2_2") (pintype "unspecified"))
    )
    (net (code "142") (name "Net-(U26-XO)") (class "Default")
      (node (ref "C56") (pin "2") (pinfunction "2_2") (pintype "input"))
      (node (ref "U26") (pin "8") (pinfunction "XO_8") (pintype "unspecified"))
      (node (ref "Y1") (pin "1") (pinfunction "OSC1_1") (pintype "unspecified"))
    )
    (net (code "143") (name "VIN24V") (class "Default")
      (node (ref "D1") (pin "2") (pinfunction "2_2") (pintype "unspecified"))
      (node (ref "D2") (pin "2") (pinfunction "2_2") (pintype "unspecified"))
      (node (ref "DC1") (pin "1") (pinfunction "1_1") (pintype "unspecified"))
      (node (ref "P9") (pin "1") (pinfunction "1_1") (pintype "unspecified"))
    )
    (net (code "144") (name "unconnected-(C44-Pad1)") (class "Default")
      (node (ref "C44") (pin "1") (pinfunction "1_1") (pintype "input"))
    )
    (net (code "145") (name "unconnected-(C44-Pad2)") (class "Default")
      (node (ref "C44") (pin "2") (pinfunction "2_2") (pintype "input"))
    )
    (net (code "146") (name "unconnected-(C52-Pad1)") (class "Default")
      (node (ref "C52") (pin "1") (pinfunction "1_1") (pintype "input"))
    )
    (net (code "147") (name "unconnected-(C52-Pad2)") (class "Default")
      (node (ref "C52") (pin "2") (pinfunction "2_2") (pintype "input"))
    )
    (net (code "148") (name "unconnected-(LED4-A-Pad2)") (class "Default")
      (node (ref "LED4") (pin "2") (pinfunction "A_2") (pintype "unspecified"))
    )
    (net (code "149") (name "unconnected-(LED4-K-Pad1)") (class "Default")
      (node (ref "LED4") (pin "1") (pinfunction "K_1") (pintype "unspecified"))
    )
    (net (code "150") (name "unconnected-(P29-Pad2)") (class "Default")
      (node (ref "P29") (pin "2") (pinfunction "2_2") (pintype "unspecified+no_connect"))
    )
    (net (code "151") (name "unconnected-(R17-Pad1)") (class "Default")
      (node (ref "R17") (pin "1") (pinfunction "1_1") (pintype "unspecified"))
    )
    (net (code "152") (name "unconnected-(R17-Pad2)") (class "Default")
      (node (ref "R17") (pin "2") (pinfunction "2_2") (pintype "unspecified"))
    )
    (net (code "153") (name "unconnected-(U5-NC-Pad28)") (class "Default")
      (node (ref "U5") (pin "28") (pinfunction "NC_28") (pintype "unspecified+no_connect"))
    )
    (net (code "154") (name "unconnected-(U5-NC-Pad29)") (class "Default")
      (node (ref "U5") (pin "29") (pinfunction "NC_29") (pintype "unspecified+no_connect"))
    )
    (net (code "155") (name "unconnected-(U5-NC-Pad30)") (class "Default")
      (node (ref "U5") (pin "30") (pinfunction "NC_30") (pintype "unspecified+no_connect"))
    )
    (net (code "156") (name "unconnected-(U8-DAT1-Pad8)") (class "Default")
      (node (ref "U8") (pin "8") (pinfunction "DAT1_8") (pintype "unspecified"))
    )
    (net (code "157") (name "unconnected-(U8-DAT2-Pad1)") (class "Default")
      (node (ref "U8") (pin "1") (pinfunction "DAT2_1") (pintype "unspecified"))
    )
    (net (code "158") (name "unconnected-(U20-NC-Pad1)") (class "Default")
      (node (ref "U20") (pin "1") (pinfunction "NC_1") (pintype "unspecified"))
    )
    (net (code "159") (name "unconnected-(U24-NC-Pad1)") (class "Default")
      (node (ref "U24") (pin "1") (pinfunction "NC_1") (pintype "unspecified"))
    )
    (net (code "160") (name "unconnected-(U25-NC-Pad1)") (class "Default")
      (node (ref "U25") (pin "1") (pinfunction "NC_1") (pintype "unspecified"))
    )
    (net (code "161") (name "unconnected-(U26-CTS#-Pad9)") (class "Default")
      (node (ref "U26") (pin "9") (pinfunction "CTS#_9") (pintype "unspecified"))
    )
    (net (code "162") (name "unconnected-(U26-DCD#-Pad12)") (class "Default")
      (node (ref "U26") (pin "12") (pinfunction "DCD#_12") (pintype "unspecified"))
    )
    (net (code "163") (name "unconnected-(U26-DSR#-Pad10)") (class "Default")
      (node (ref "U26") (pin "10") (pinfunction "DSR#_10") (pintype "unspecified"))
    )
    (net (code "164") (name "unconnected-(U26-R232-Pad15)") (class "Default")
      (node (ref "U26") (pin "15") (pinfunction "R232_15") (pintype "unspecified"))
    )
    (net (code "165") (name "unconnected-(U26-RI#-Pad11)") (class "Default")
      (node (ref "U26") (pin "11") (pinfunction "RI#_11") (pintype "unspecified"))
    )
    (net (code "166") (name "unconnected-(USB2-SBU1-Pad9)") (class "Default")
      (node (ref "USB2") (pin "9") (pinfunction "SBU1_9") (pintype "unspecified+no_connect"))
    )
    (net (code "167") (name "unconnected-(USB2-SBU2-Pad3)") (class "Default")
      (node (ref "USB2") (pin "3") (pinfunction "SBU2_3") (pintype "unspecified+no_connect"))
    )
    (net (code "168") (name "unconnected-(USB8-CC1-PadA5)") (class "Default")
      (node (ref "USB8") (pin "A5") (pinfunction "CC1_A5") (pintype "unspecified"))
    )
    (net (code "169") (name "unconnected-(USB8-CC2-PadB5)") (class "Default")
      (node (ref "USB8") (pin "B5") (pinfunction "CC2_B5") (pintype "unspecified"))
    )
    (net (code "170") (name "unconnected-(USB8-GND-PadA1B12)") (class "Default")
      (node (ref "USB8") (pin "A1B12") (pinfunction "GND_A1B12") (pintype "unspecified"))
    )
    (net (code "171") (name "unconnected-(USB8-GND-PadB1A12)") (class "Default")
      (node (ref "USB8") (pin "B1A12") (pinfunction "GND_B1A12") (pintype "unspecified"))
    )
    (net (code "172") (name "unconnected-(USB8-Pad1)") (class "Default")
      (node (ref "USB8") (pin "1") (pinfunction "1_1") (pintype "unspecified"))
    )
    (net (code "173") (name "unconnected-(USB8-Pad2)") (class "Default")
      (node (ref "USB8") (pin "2") (pinfunction "2_2") (pintype "unspecified"))
    )
    (net (code "174") (name "unconnected-(USB8-Pad3)") (class "Default")
      (node (ref "USB8") (pin "3") (pinfunction "3_3") (pintype "unspecified"))
    )
    (net (code "175") (name "unconnected-(USB8-Pad4)") (class "Default")
      (node (ref "USB8") (pin "4") (pinfunction "4_4") (pintype "unspecified"))
    )
    (net (code "176") (name "unconnected-(USB8-SBU1-PadA8)") (class "Default")
      (node (ref "USB8") (pin "A8") (pinfunction "SBU1_A8") (pintype "unspecified"))
    )
    (net (code "177") (name "unconnected-(USB8-SBU2-PadB8)") (class "Default")
      (node (ref "USB8") (pin "B8") (pinfunction "SBU2_B8") (pintype "unspecified"))
    )
    (net (code "178") (name "unconnected-(USB8-VBUS-PadA4B9)") (class "Default")
      (node (ref "USB8") (pin "A4B9") (pinfunction "VBUS_A4B9") (pintype "unspecified"))
    )
    (net (code "179") (name "unconnected-(USB8-VBUS-PadB4A9)") (class "Default")
      (node (ref "USB8") (pin "B4A9") (pinfunction "VBUS_B4A9") (pintype "unspecified"))
    )
  )
)
